# RFWBBoard.net
KiCad netlist of a schematic drawn in EAGLE
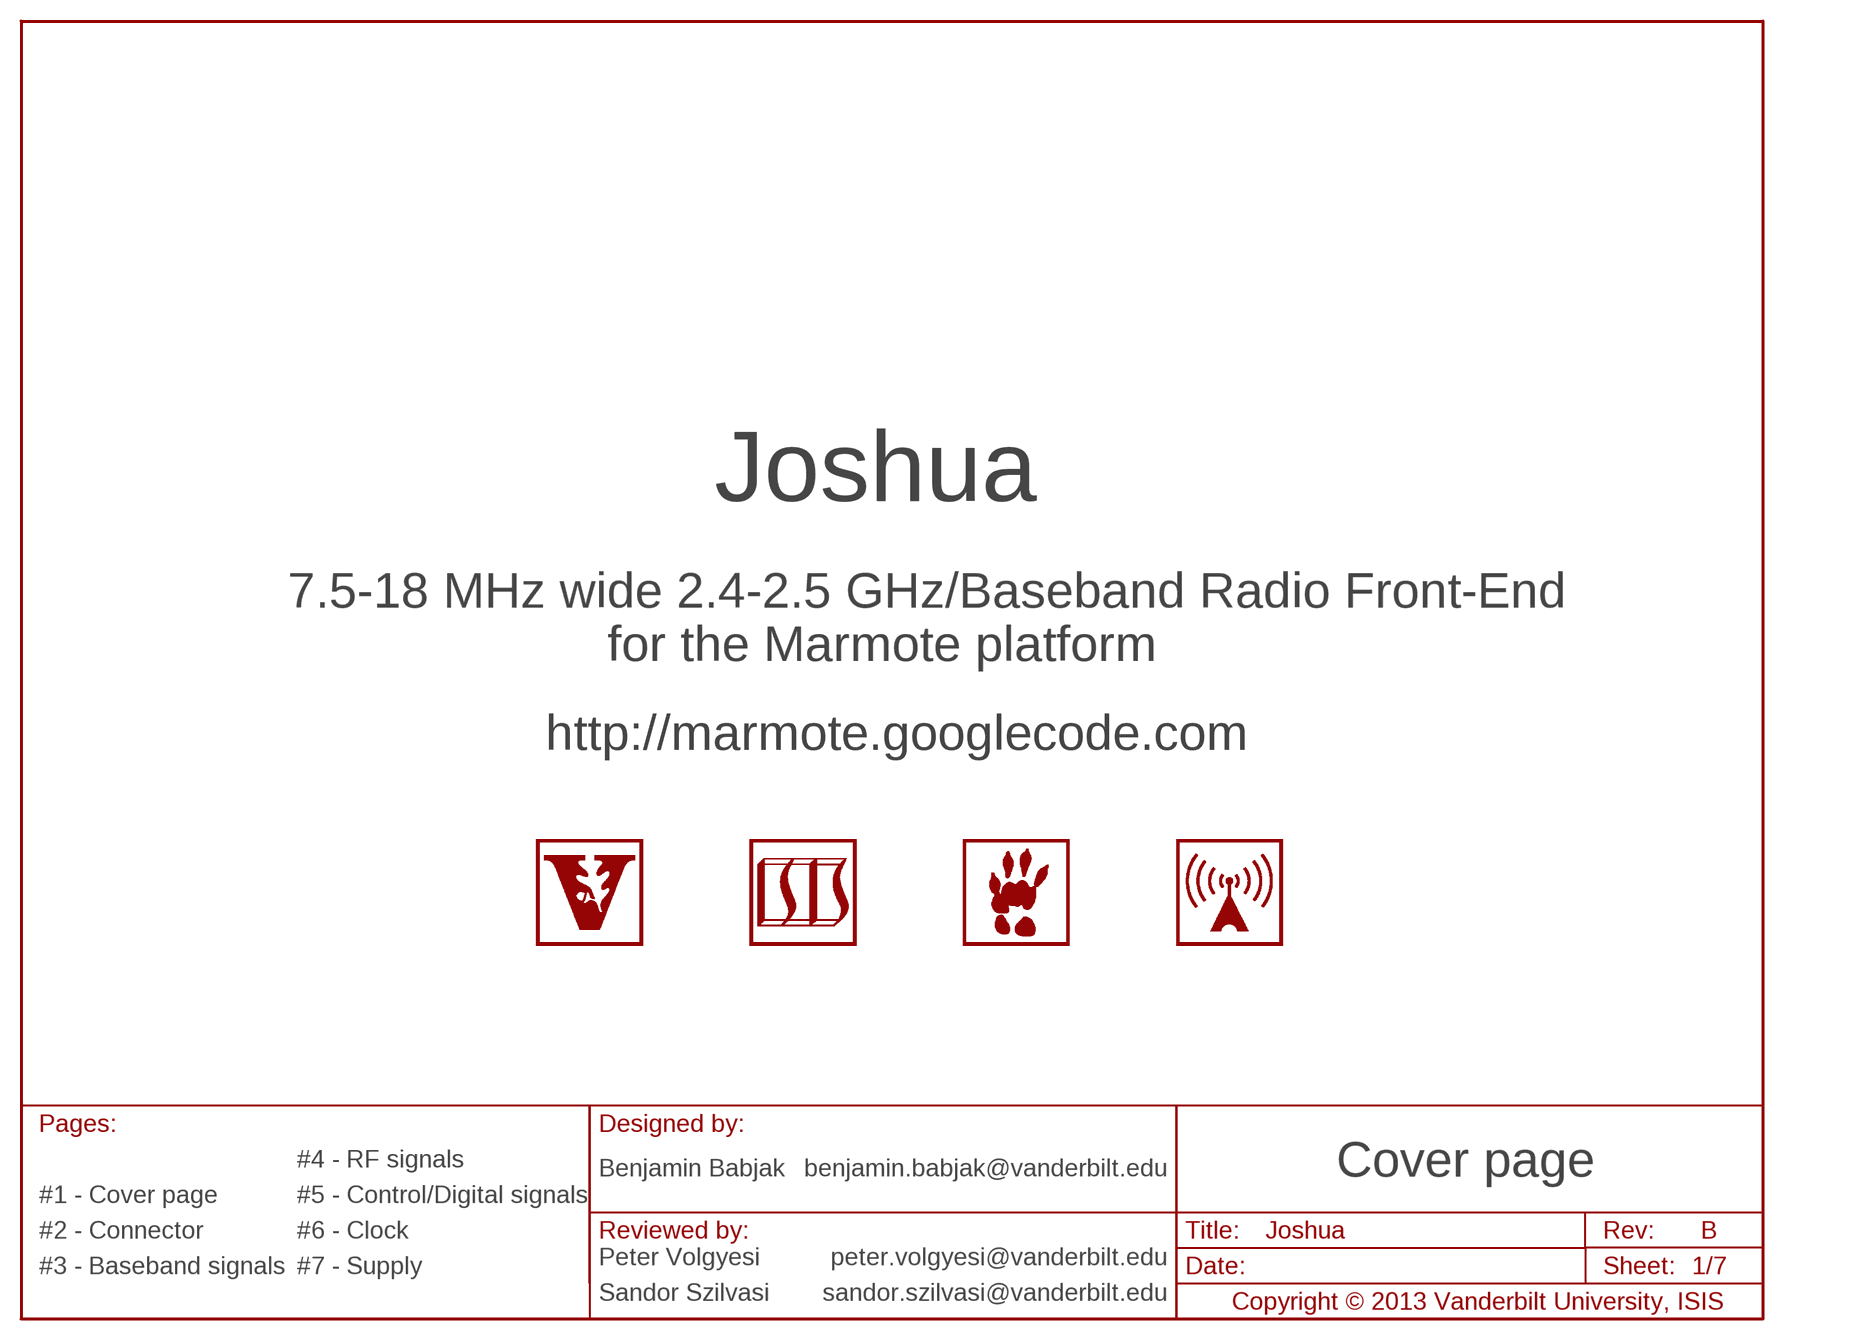
[diagram p0: schematic, sheet 1]
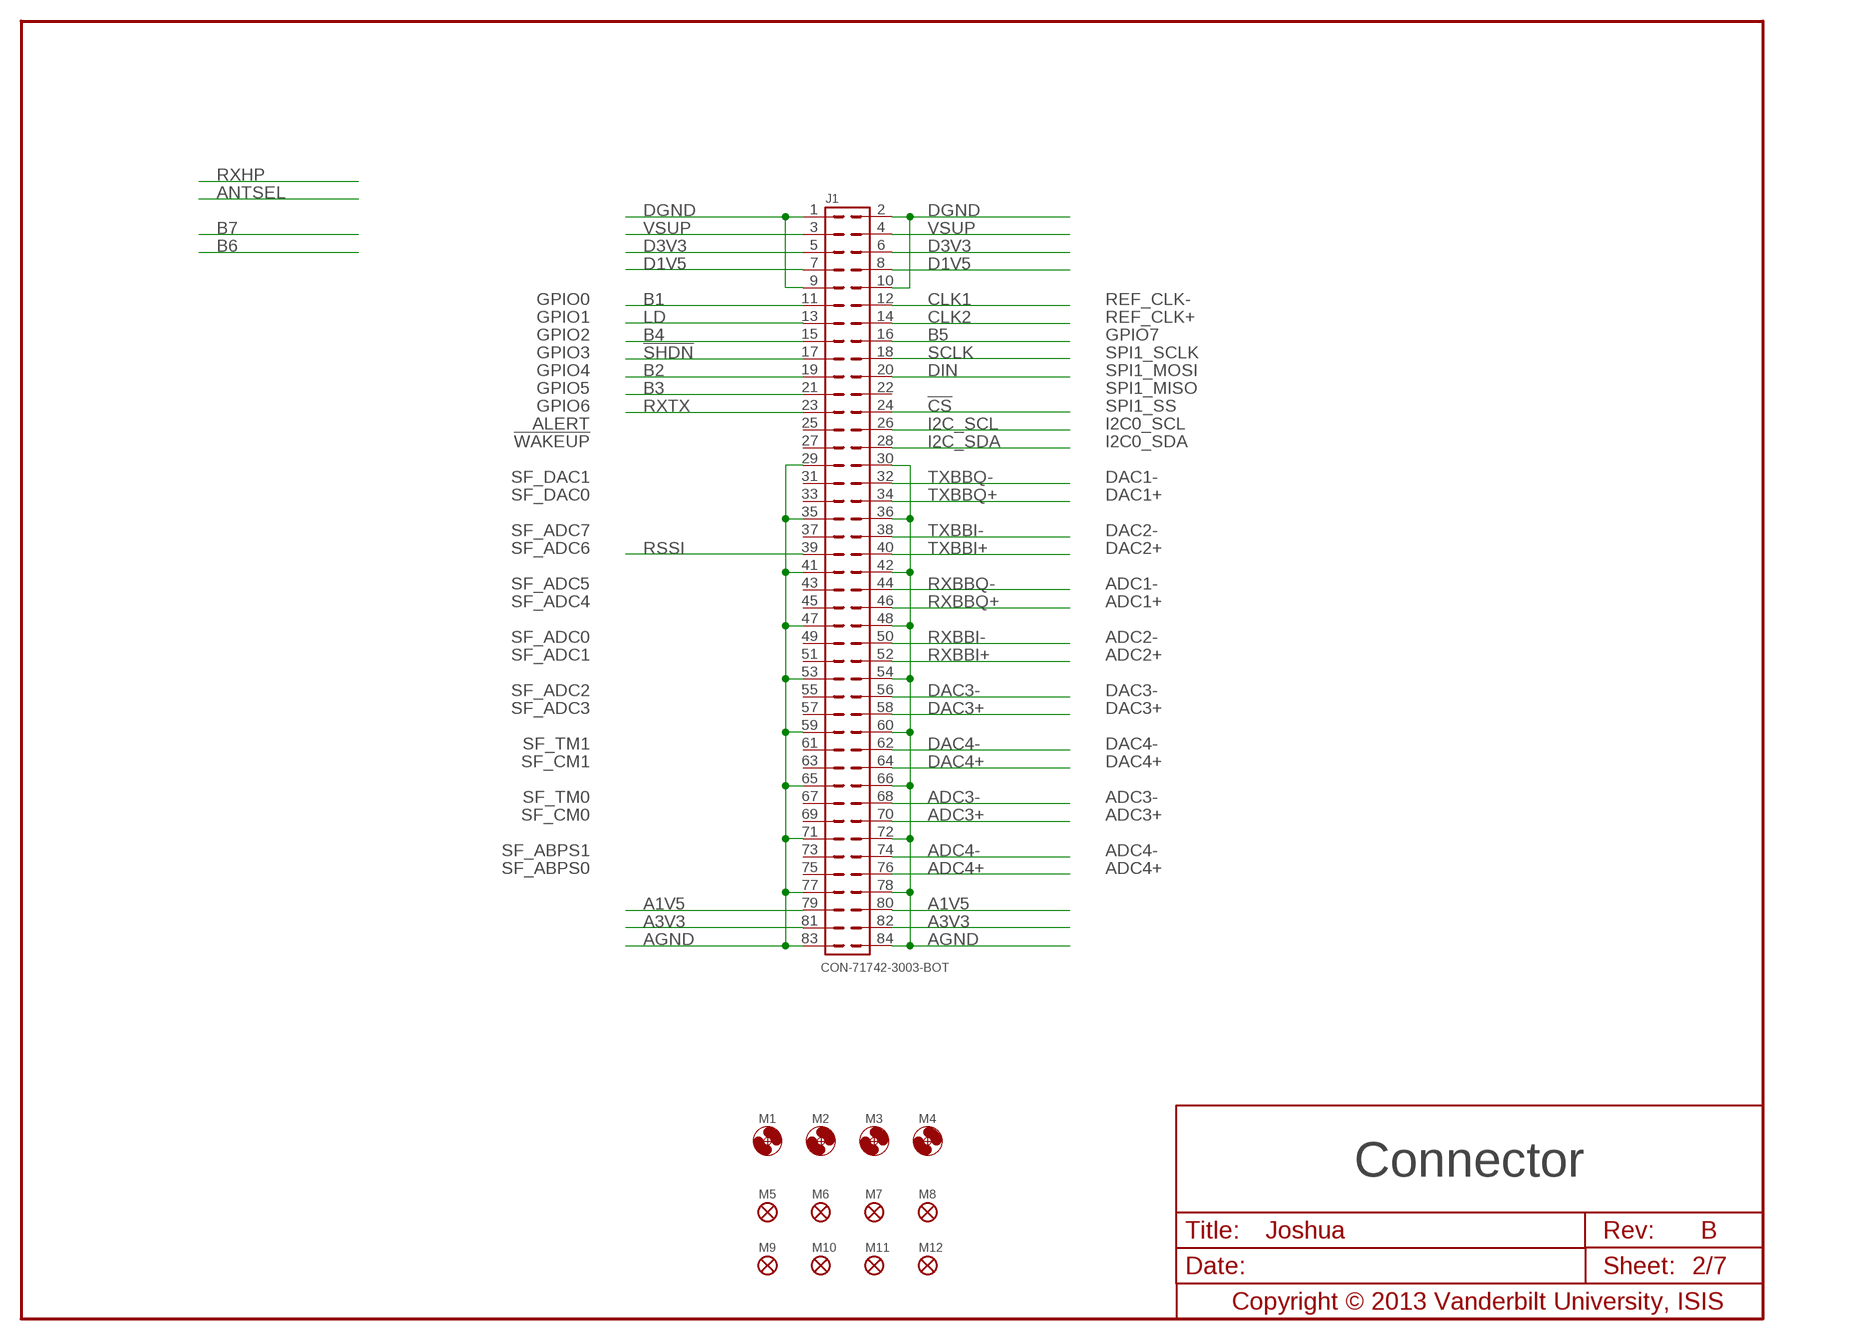
[diagram p1: schematic, sheet 2]
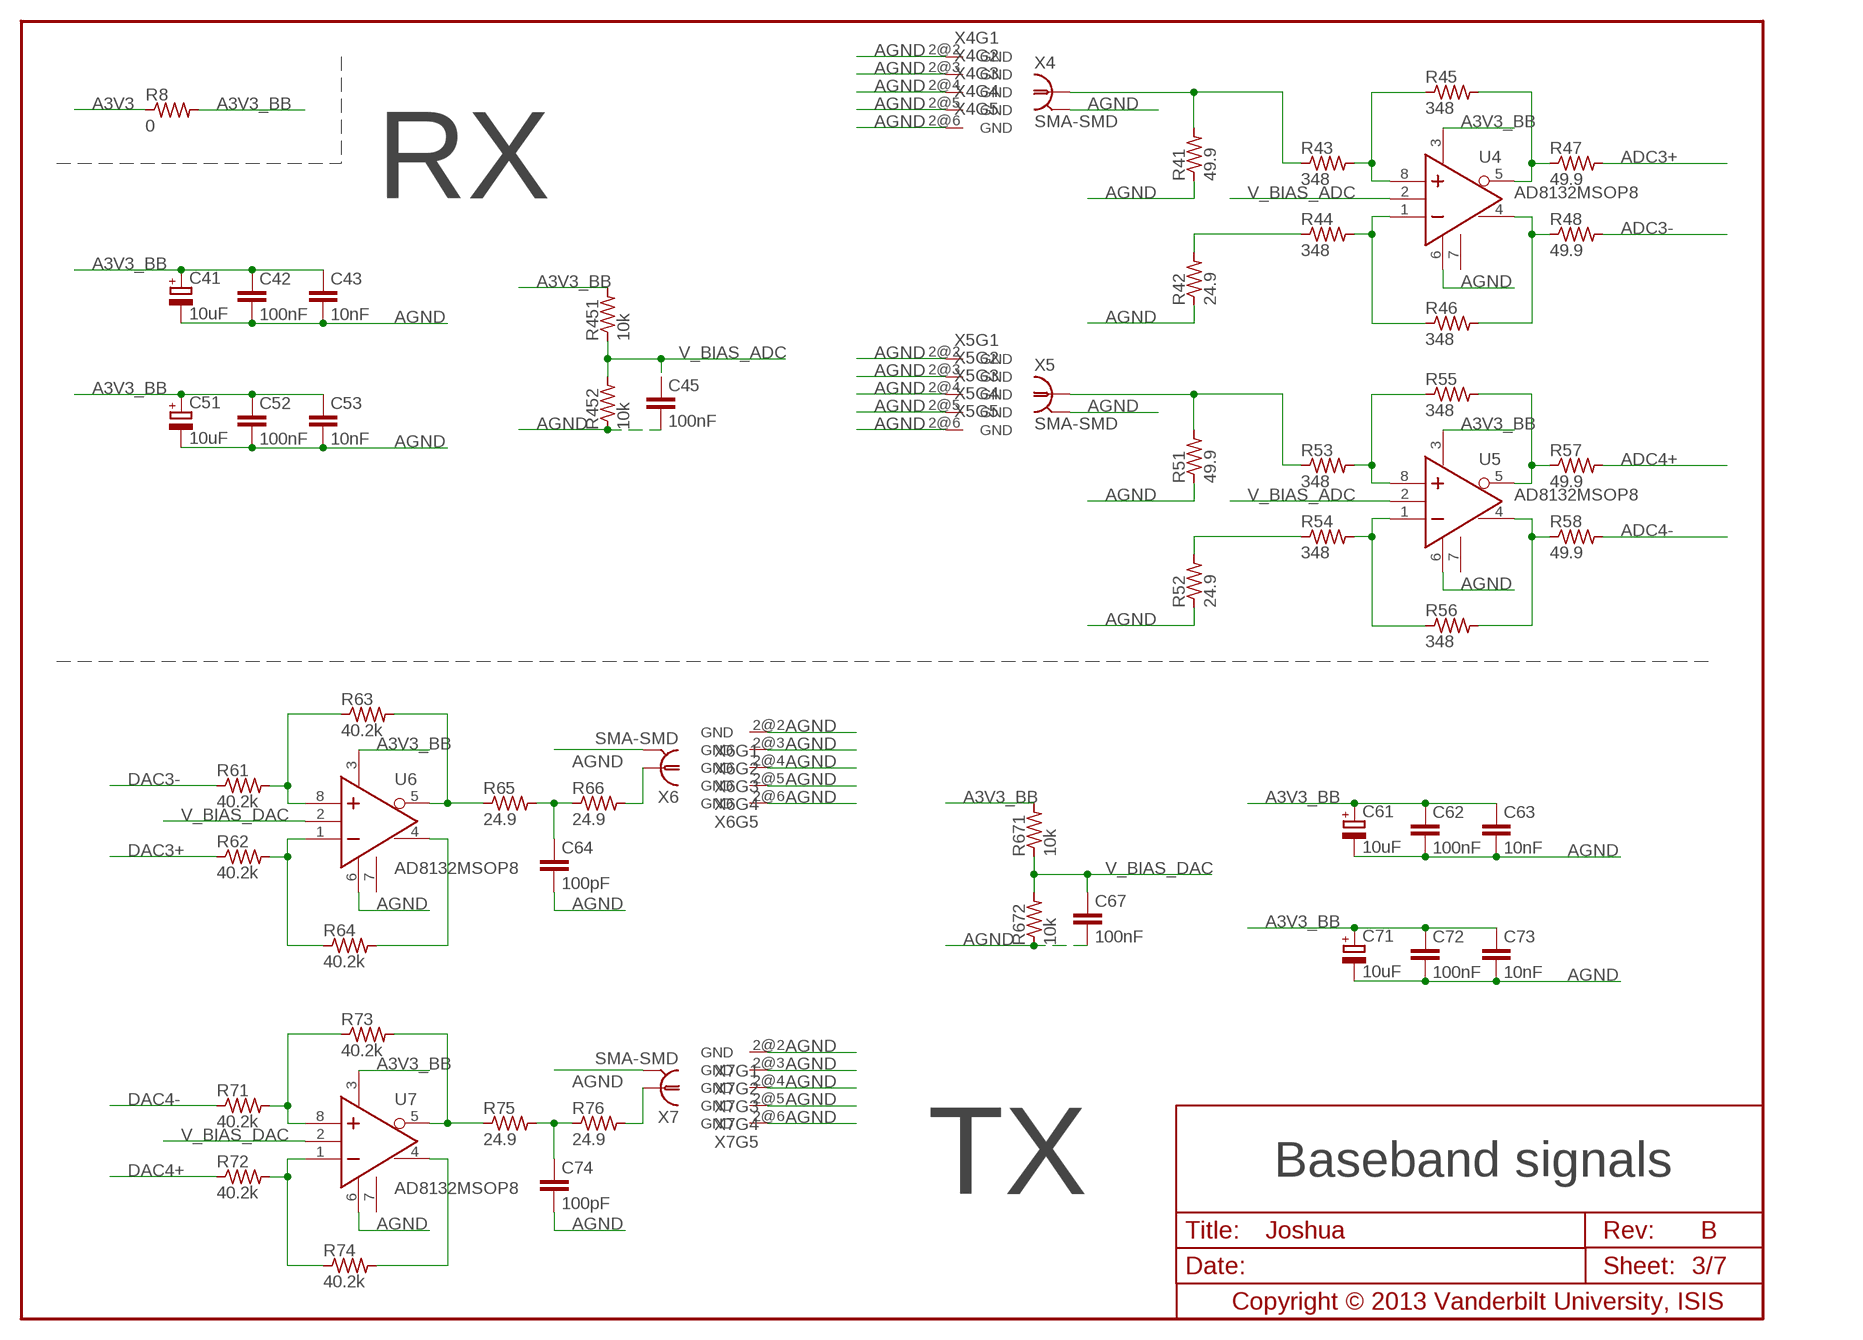
[diagram p2: schematic, sheet 3]
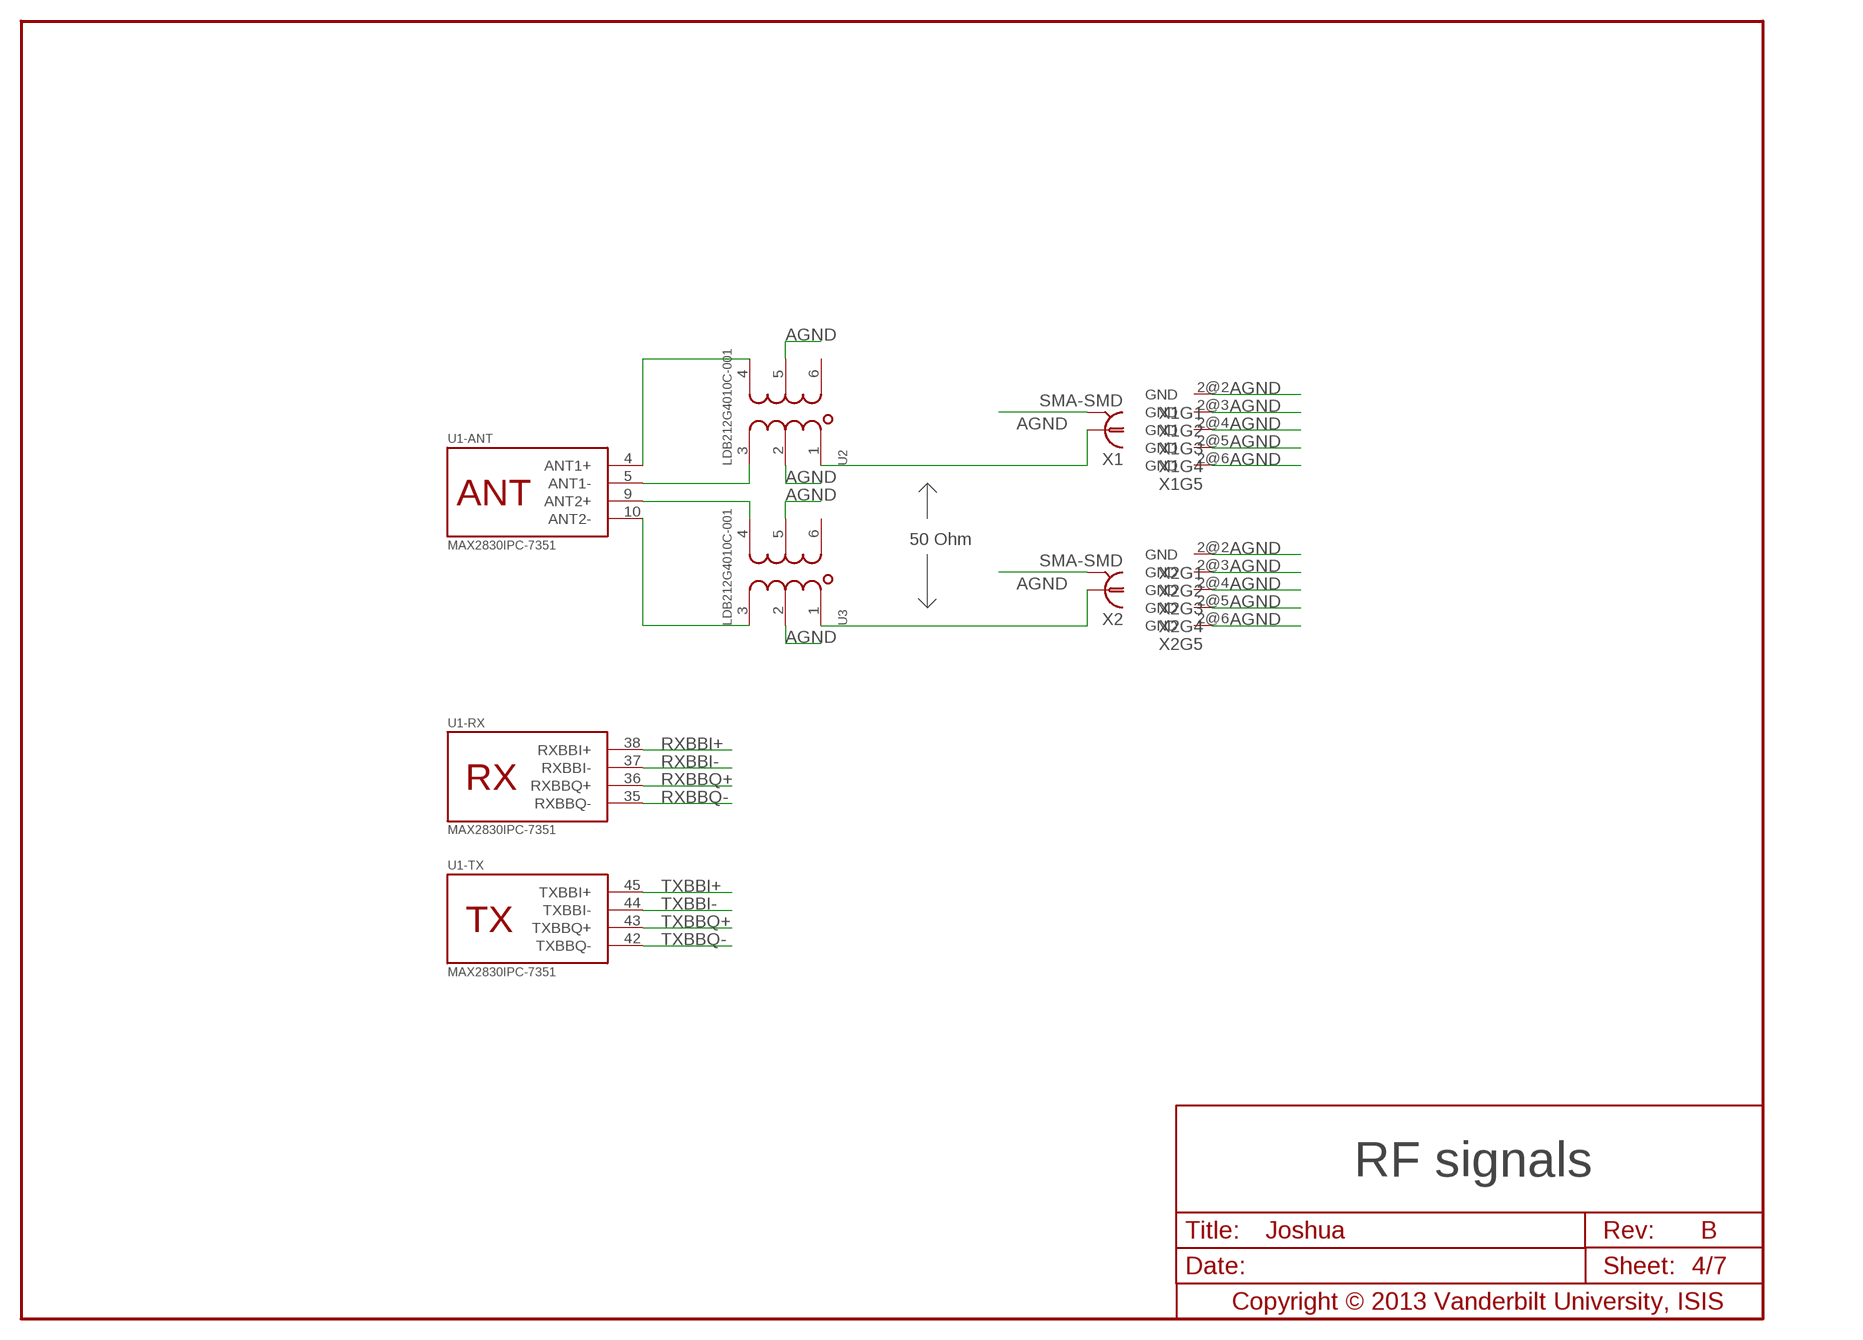
[diagram p3: schematic, sheet 4]
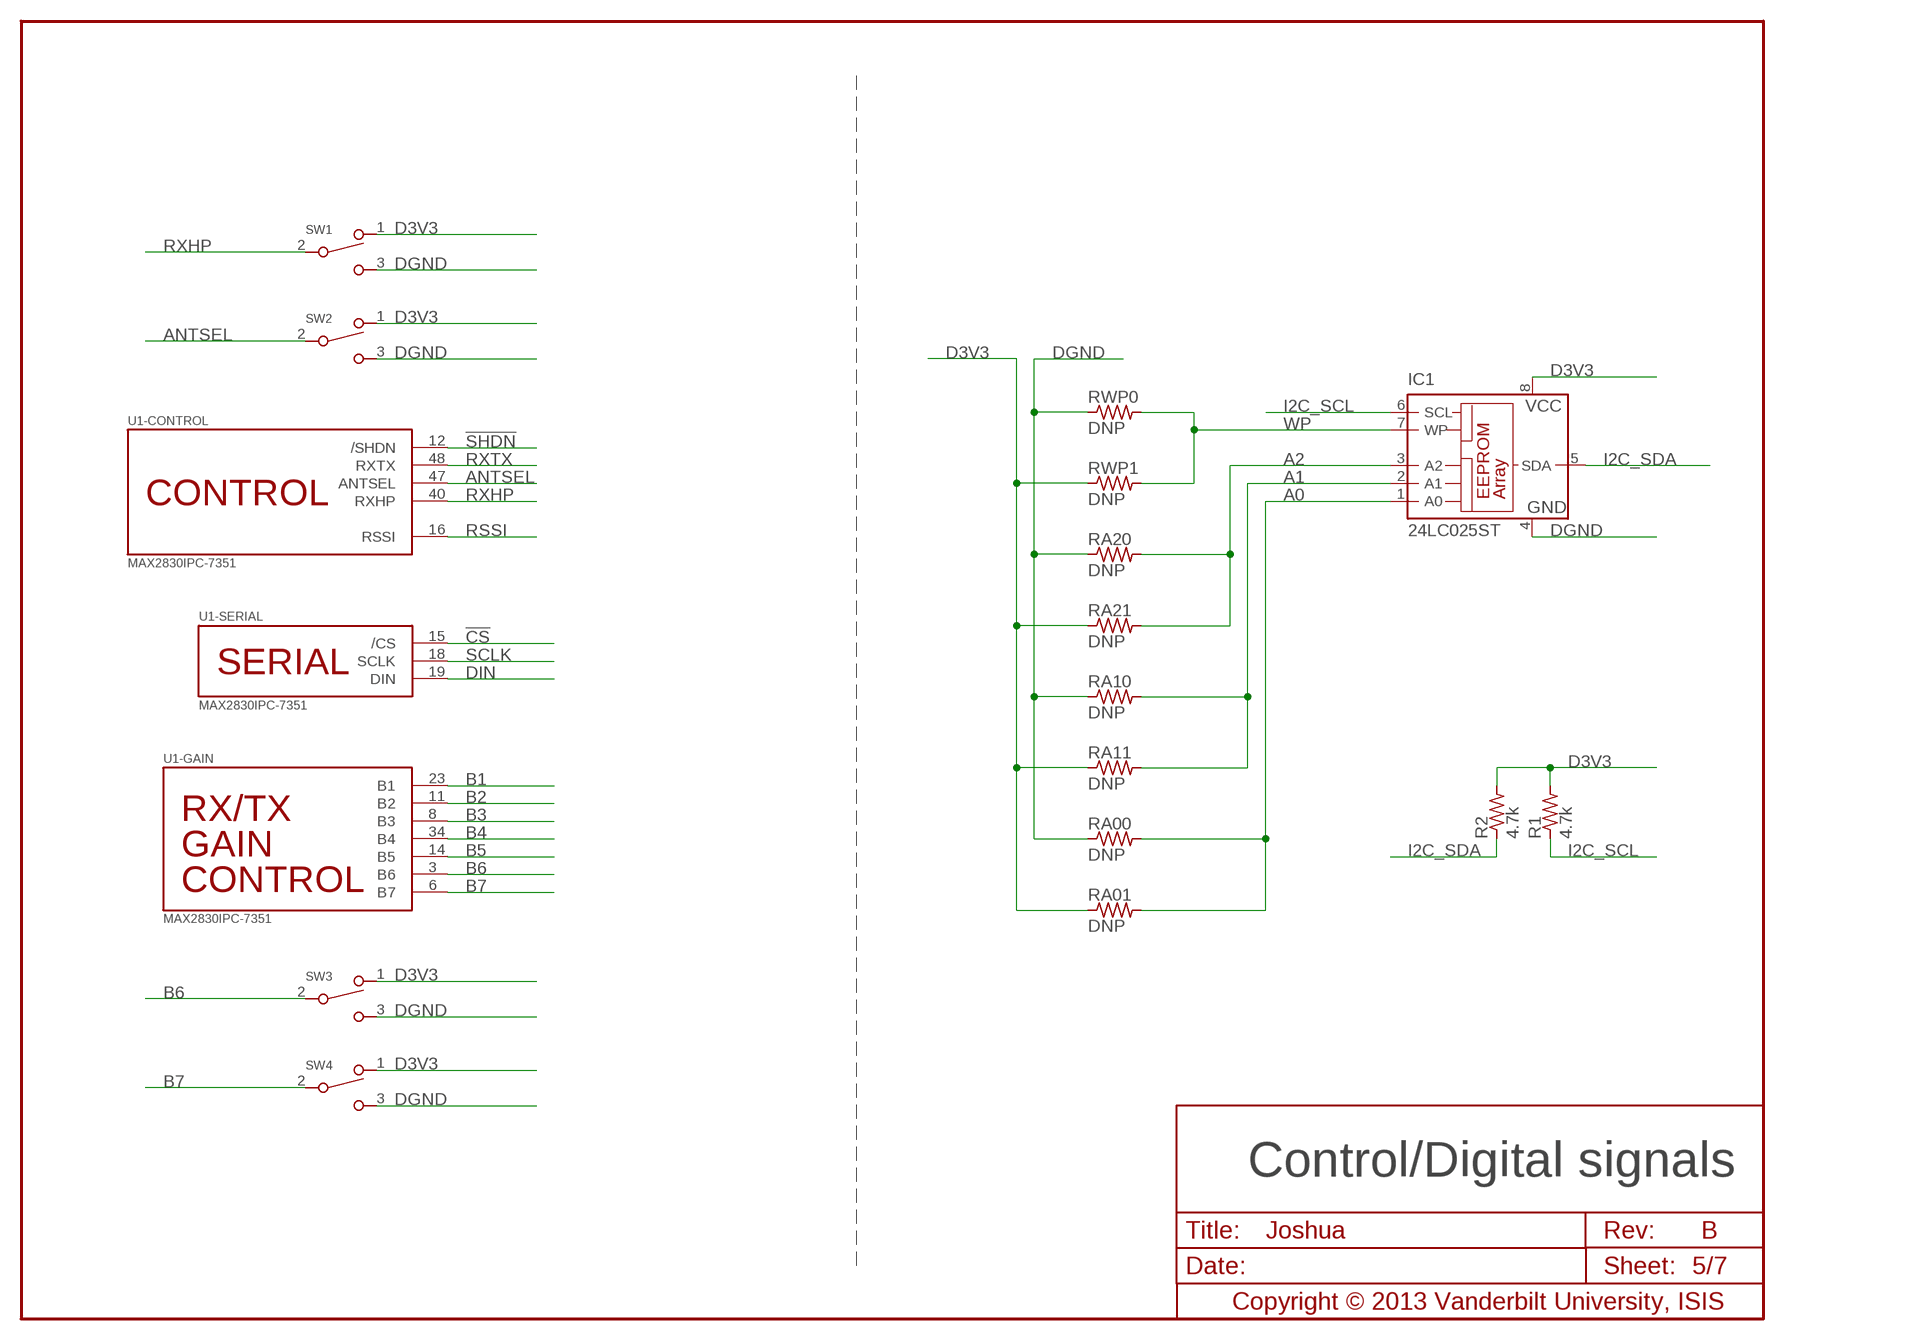
[diagram p4: schematic, sheet 5]
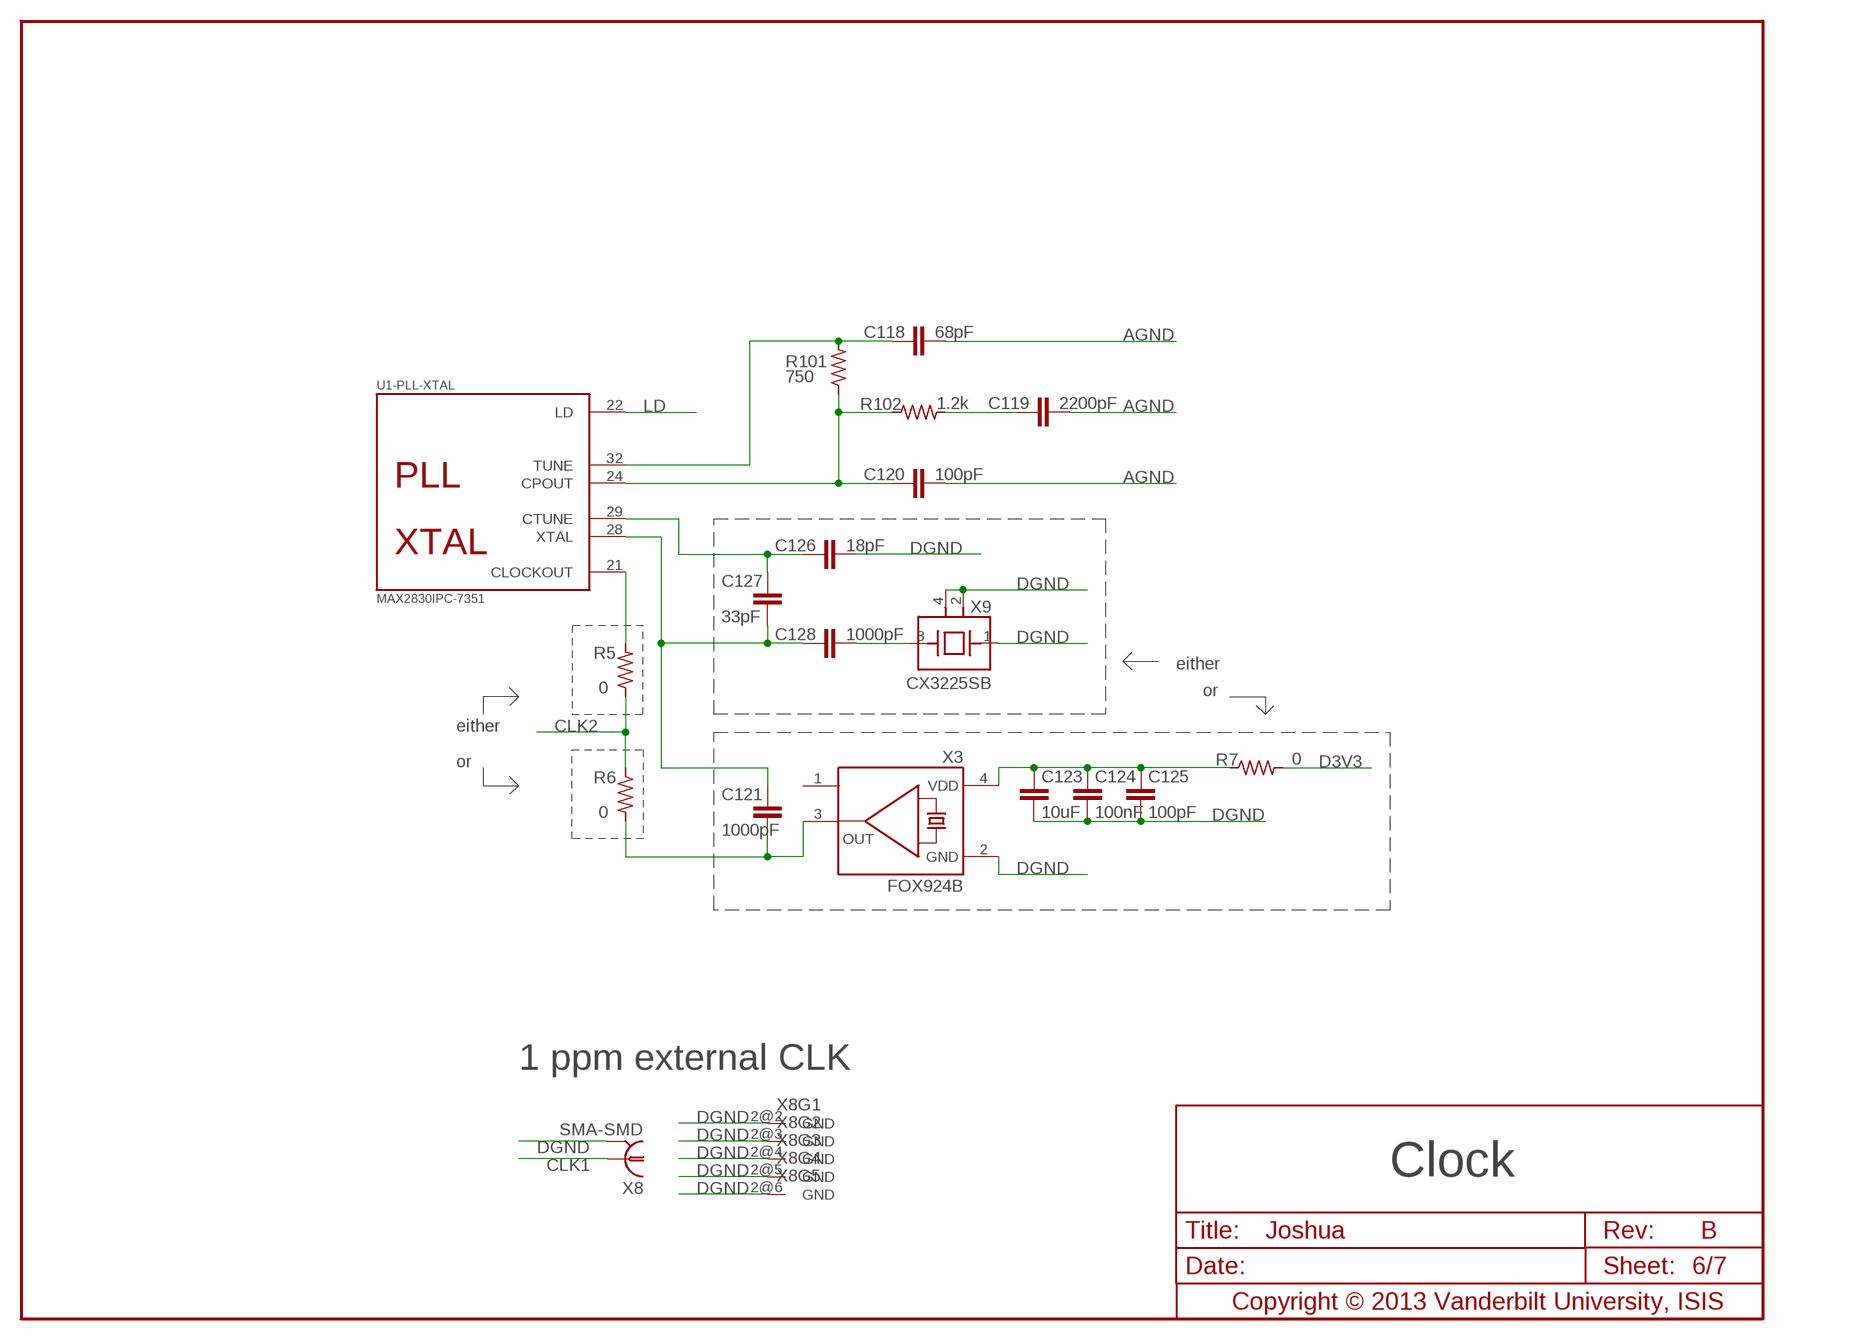
[diagram p5: schematic, sheet 6]
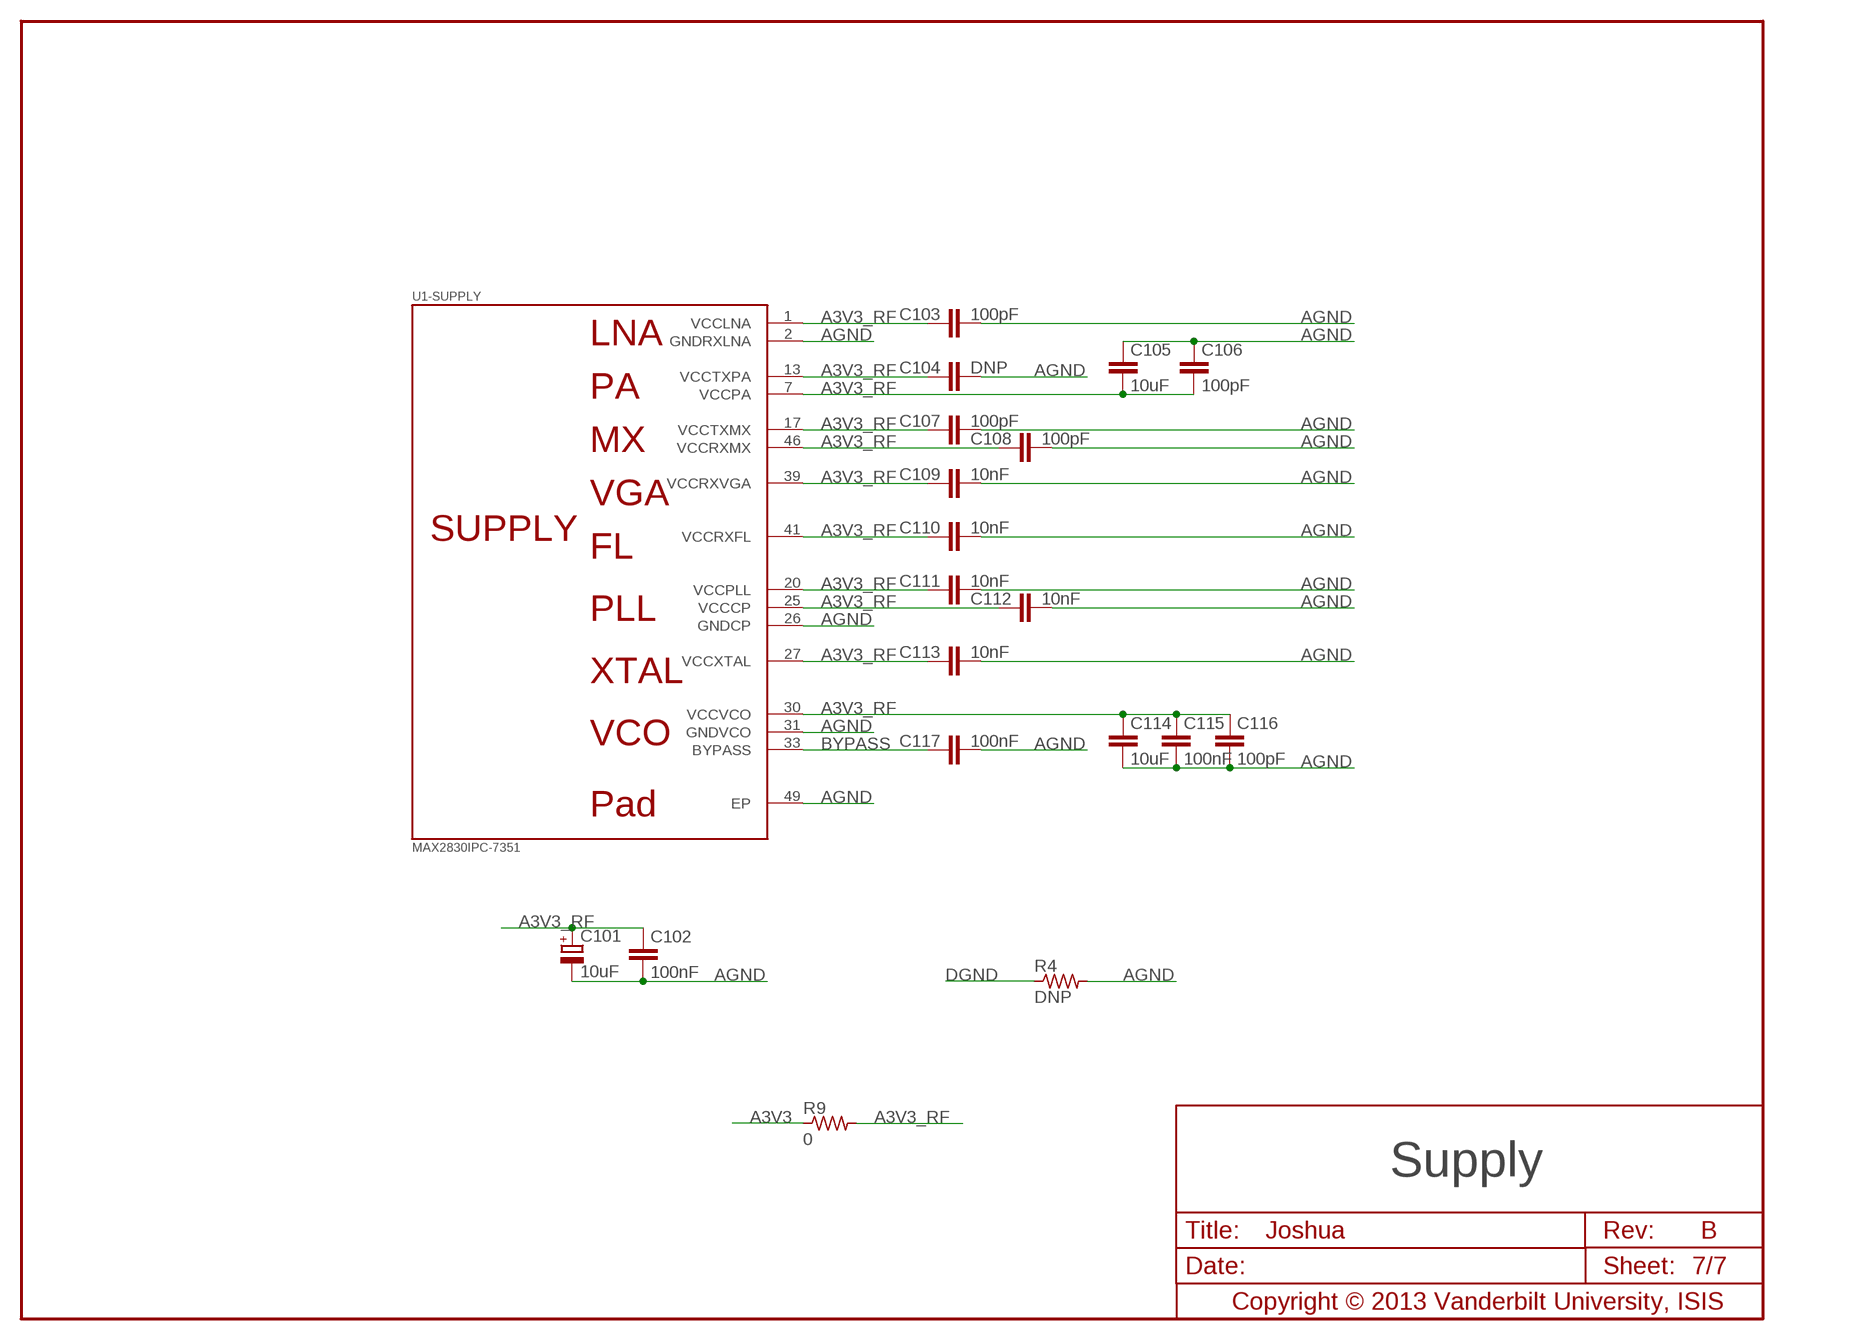
[diagram p6: schematic, sheet 7]

(export (version "E")
  (design (tool "Eeschema 10.0.6"))
  (components
    (comp (ref "LOGO4")
      (value "LOGO-ISIS-600MIL-10MM-SS")
      (footprint "eagle-import:LOGO-ISIS-10MM-SILKSCREEN")
      (libsource (lib "eagle-import") (part "LOGO-ISIS-600MIL-10MM-SS"))
    )
    (comp (ref "LOGO5")
      (value "LOGO-VANDERBILT-600MIL-10MM-SS")
      (footprint "eagle-import:LOGO-VANDERBILT-10MM-SILKSCREEN")
      (libsource (lib "eagle-import") (part "LOGO-VANDERBILT-600MIL-10MM-SS"))
    )
    (comp (ref "LOGO6")
      (value "LOGO-MARMOTE-600MIL-10MM-SS")
      (footprint "eagle-import:LOGO-MARMOTE-10MM-SILKSCREEN")
      (libsource (lib "eagle-import") (part "LOGO-MARMOTE-600MIL-10MM-SS"))
    )
    (comp (ref "LOGO7")
      (value "LOGO-RADIO-3-600MIL-10MM-SS")
      (footprint "eagle-import:LOGO-RADIO-FILLED-10MM-SILKSCREEN")
      (libsource (lib "eagle-import") (part "LOGO-RADIO-3-600MIL-10MM-SS"))
    )
    (comp (ref "U1")
      (value "MAX2830IPC-7351")
      (footprint "eagle-import:TQFN-48")
      (libsource (lib "eagle-import") (part "MAX2830IPC-7351"))
    )
    (comp (ref "U2")
      (value "LDB212G4010C-001")
      (footprint "eagle-import:LDB21-FOOTPRINT")
      (libsource (lib "eagle-import") (part "LDB212G4010C-001"))
    )
    (comp (ref "U3")
      (value "LDB212G4010C-001")
      (footprint "eagle-import:LDB21-FOOTPRINT")
      (libsource (lib "eagle-import") (part "LDB212G4010C-001"))
    )
    (comp (ref "X1")
      (value "SMA-SMD")
      (footprint "eagle-import:SMA-SMD")
      (libsource (lib "eagle-import") (part "SMA-SMD"))
    )
    (comp (ref "X2")
      (value "SMA-SMD")
      (footprint "eagle-import:SMA-SMD")
      (libsource (lib "eagle-import") (part "SMA-SMD"))
    )
    (comp (ref "J1")
      (value "CON-71742-3003-BOT")
      (footprint "eagle-import:71742-3003-BOT")
      (libsource (lib "eagle-import") (part "CON-71742-3003-BOT"))
    )
    (comp (ref "M1")
      (value "MOUNT-HOLE3.3")
      (footprint "eagle-import:3,3")
      (libsource (lib "eagle-import") (part "MOUNT-HOLE3.3"))
    )
    (comp (ref "M2")
      (value "MOUNT-HOLE3.3")
      (footprint "eagle-import:3,3")
      (libsource (lib "eagle-import") (part "MOUNT-HOLE3.3"))
    )
    (comp (ref "M3")
      (value "MOUNT-HOLE3.3")
      (footprint "eagle-import:3,3")
      (libsource (lib "eagle-import") (part "MOUNT-HOLE3.3"))
    )
    (comp (ref "M4")
      (value "MOUNT-HOLE3.3")
      (footprint "eagle-import:3,3")
      (libsource (lib "eagle-import") (part "MOUNT-HOLE3.3"))
    )
    (comp (ref "M5")
      (value "FIDUCIAL1X2")
      (footprint "eagle-import:FIDUCIAL-1X2")
      (libsource (lib "eagle-import") (part "FIDUCIAL1X2"))
    )
    (comp (ref "M6")
      (value "FIDUCIAL1X2")
      (footprint "eagle-import:FIDUCIAL-1X2")
      (libsource (lib "eagle-import") (part "FIDUCIAL1X2"))
    )
    (comp (ref "M7")
      (value "FIDUCIAL1X2")
      (footprint "eagle-import:FIDUCIAL-1X2")
      (libsource (lib "eagle-import") (part "FIDUCIAL1X2"))
    )
    (comp (ref "M8")
      (value "FIDUCIAL1X2")
      (footprint "eagle-import:FIDUCIAL-1X2")
      (libsource (lib "eagle-import") (part "FIDUCIAL1X2"))
    )
    (comp (ref "M9")
      (value "FIDUCIAL1X2")
      (footprint "eagle-import:FIDUCIAL-1X2")
      (libsource (lib "eagle-import") (part "FIDUCIAL1X2"))
    )
    (comp (ref "M10")
      (value "FIDUCIAL1X2")
      (footprint "eagle-import:FIDUCIAL-1X2")
      (libsource (lib "eagle-import") (part "FIDUCIAL1X2"))
    )
    (comp (ref "M11")
      (value "FIDUCIAL1X2")
      (footprint "eagle-import:FIDUCIAL-1X2")
      (libsource (lib "eagle-import") (part "FIDUCIAL1X2"))
    )
    (comp (ref "M12")
      (value "FIDUCIAL1X2")
      (footprint "eagle-import:FIDUCIAL-1X2")
      (libsource (lib "eagle-import") (part "FIDUCIAL1X2"))
    )
    (comp (ref "IC1")
      (value "24LC025ST")
      (footprint "eagle-import:TSSOP8")
      (fields (field (name "MF") "MICROCHIP") (field (name "MPN") "24LC025-I/ST"))
      (libsource (lib "eagle-import") (part "24STLC025"))
    )
    (comp (ref "R1")
      (value "4.7k")
      (footprint "eagle-import:R0402")
      (libsource (lib "eagle-import") (part "R0402"))
    )
    (comp (ref "R2")
      (value "4.7k")
      (footprint "eagle-import:R0402")
      (libsource (lib "eagle-import") (part "R0402"))
    )
    (comp (ref "RA00")
      (value "DNP")
      (footprint "eagle-import:R0402")
      (libsource (lib "eagle-import") (part "R0402"))
    )
    (comp (ref "RA01")
      (value "DNP")
      (footprint "eagle-import:R0402")
      (libsource (lib "eagle-import") (part "R0402"))
    )
    (comp (ref "RA10")
      (value "DNP")
      (footprint "eagle-import:R0402")
      (libsource (lib "eagle-import") (part "R0402"))
    )
    (comp (ref "RA11")
      (value "DNP")
      (footprint "eagle-import:R0402")
      (libsource (lib "eagle-import") (part "R0402"))
    )
    (comp (ref "RA20")
      (value "DNP")
      (footprint "eagle-import:R0402")
      (libsource (lib "eagle-import") (part "R0402"))
    )
    (comp (ref "RA21")
      (value "DNP")
      (footprint "eagle-import:R0402")
      (libsource (lib "eagle-import") (part "R0402"))
    )
    (comp (ref "RWP0")
      (value "DNP")
      (footprint "eagle-import:R0402")
      (libsource (lib "eagle-import") (part "R0402"))
    )
    (comp (ref "RWP1")
      (value "DNP")
      (footprint "eagle-import:R0402")
      (libsource (lib "eagle-import") (part "R0402"))
    )
    (comp (ref "SW1")
      (value "SWITCH-CJS-1200TA")
      (footprint "eagle-import:SWITCH-DIP-CJS")
      (fields (field (name "MF") "CJS") (field (name "MPN") "CJS-1200TA"))
      (libsource (lib "eagle-import") (part "SWITCH-CJS-1200TA"))
    )
    (comp (ref "SW2")
      (value "SWITCH-CJS-1200TA")
      (footprint "eagle-import:SWITCH-DIP-CJS")
      (fields (field (name "MF") "CJS") (field (name "MPN") "CJS-1200TA"))
      (libsource (lib "eagle-import") (part "SWITCH-CJS-1200TA"))
    )
    (comp (ref "SW3")
      (value "SWITCH-CJS-1200TA")
      (footprint "eagle-import:SWITCH-DIP-CJS")
      (fields (field (name "MF") "CJS") (field (name "MPN") "CJS-1200TA"))
      (libsource (lib "eagle-import") (part "SWITCH-CJS-1200TA"))
    )
    (comp (ref "SW4")
      (value "SWITCH-CJS-1200TA")
      (footprint "eagle-import:SWITCH-DIP-CJS")
      (fields (field (name "MF") "CJS") (field (name "MPN") "CJS-1200TA"))
      (libsource (lib "eagle-import") (part "SWITCH-CJS-1200TA"))
    )
    (comp (ref "C101")
      (value "10uF")
      (footprint "eagle-import:CPOL2012")
      (libsource (lib "eagle-import") (part "CPOL2012"))
    )
    (comp (ref "C102")
      (value "100nF")
      (footprint "eagle-import:C0402")
      (libsource (lib "eagle-import") (part "C0402"))
    )
    (comp (ref "C103")
      (value "100pF")
      (footprint "eagle-import:C0402")
      (libsource (lib "eagle-import") (part "C0402"))
    )
    (comp (ref "C104")
      (value "DNP")
      (footprint "eagle-import:C0402")
      (libsource (lib "eagle-import") (part "C0402"))
    )
    (comp (ref "C105")
      (value "10uF")
      (footprint "eagle-import:C1206")
      (libsource (lib "eagle-import") (part "C1206"))
    )
    (comp (ref "C106")
      (value "100pF")
      (footprint "eagle-import:C0402")
      (libsource (lib "eagle-import") (part "C0402"))
    )
    (comp (ref "C107")
      (value "100pF")
      (footprint "eagle-import:C0402")
      (libsource (lib "eagle-import") (part "C0402"))
    )
    (comp (ref "C108")
      (value "100pF")
      (footprint "eagle-import:C0402")
      (libsource (lib "eagle-import") (part "C0402"))
    )
    (comp (ref "C109")
      (value "10nF")
      (footprint "eagle-import:C0402")
      (libsource (lib "eagle-import") (part "C0402"))
    )
    (comp (ref "C110")
      (value "10nF")
      (footprint "eagle-import:C0402")
      (libsource (lib "eagle-import") (part "C0402"))
    )
    (comp (ref "C111")
      (value "10nF")
      (footprint "eagle-import:C0402")
      (libsource (lib "eagle-import") (part "C0402"))
    )
    (comp (ref "C112")
      (value "10nF")
      (footprint "eagle-import:C0402")
      (libsource (lib "eagle-import") (part "C0402"))
    )
    (comp (ref "C113")
      (value "10nF")
      (footprint "eagle-import:C0402")
      (libsource (lib "eagle-import") (part "C0402"))
    )
    (comp (ref "C114")
      (value "10uF")
      (footprint "eagle-import:C0805")
      (libsource (lib "eagle-import") (part "C0805"))
    )
    (comp (ref "C115")
      (value "100nF")
      (footprint "eagle-import:C0402")
      (libsource (lib "eagle-import") (part "C0402"))
    )
    (comp (ref "C116")
      (value "100pF")
      (footprint "eagle-import:C0402")
      (libsource (lib "eagle-import") (part "C0402"))
    )
    (comp (ref "C117")
      (value "100nF")
      (footprint "eagle-import:C0402")
      (libsource (lib "eagle-import") (part "C0402"))
    )
    (comp (ref "R4")
      (value "DNP")
      (footprint "eagle-import:R1206")
      (libsource (lib "eagle-import") (part "R1206"))
    )
    (comp (ref "R9")
      (value "0")
      (footprint "eagle-import:R1206")
      (libsource (lib "eagle-import") (part "R1206"))
    )
    (comp (ref "C118")
      (value "68pF")
      (footprint "eagle-import:C0402")
      (libsource (lib "eagle-import") (part "C0402"))
    )
    (comp (ref "C119")
      (value "2200pF")
      (footprint "eagle-import:C0402")
      (libsource (lib "eagle-import") (part "C0402"))
    )
    (comp (ref "C120")
      (value "100pF")
      (footprint "eagle-import:C0402")
      (libsource (lib "eagle-import") (part "C0402"))
    )
    (comp (ref "C121")
      (value "1000pF")
      (footprint "eagle-import:C0402")
      (libsource (lib "eagle-import") (part "C0402"))
    )
    (comp (ref "C123")
      (value "10uF")
      (footprint "eagle-import:C0805")
      (libsource (lib "eagle-import") (part "C0805"))
    )
    (comp (ref "C124")
      (value "100nF")
      (footprint "eagle-import:C0402")
      (libsource (lib "eagle-import") (part "C0402"))
    )
    (comp (ref "C125")
      (value "100pF")
      (footprint "eagle-import:C0402")
      (libsource (lib "eagle-import") (part "C0402"))
    )
    (comp (ref "C126")
      (value "18pF")
      (footprint "eagle-import:C0402")
      (libsource (lib "eagle-import") (part "C0402"))
    )
    (comp (ref "C127")
      (value "33pF")
      (footprint "eagle-import:C0402")
      (libsource (lib "eagle-import") (part "C0402"))
    )
    (comp (ref "C128")
      (value "1000pF")
      (footprint "eagle-import:C0402")
      (libsource (lib "eagle-import") (part "C0402"))
    )
    (comp (ref "R5")
      (value "0")
      (footprint "eagle-import:R0402")
      (libsource (lib "eagle-import") (part "R0402"))
    )
    (comp (ref "R6")
      (value "0")
      (footprint "eagle-import:R0402")
      (libsource (lib "eagle-import") (part "R0402"))
    )
    (comp (ref "R7")
      (value "0")
      (footprint "eagle-import:R1206")
      (libsource (lib "eagle-import") (part "R1206"))
    )
    (comp (ref "R101")
      (value "750")
      (footprint "eagle-import:R0402")
      (libsource (lib "eagle-import") (part "R0402"))
    )
    (comp (ref "R102")
      (value "1.2k")
      (footprint "eagle-import:R0402")
      (libsource (lib "eagle-import") (part "R0402"))
    )
    (comp (ref "X3")
      (value "FOX924B")
      (footprint "eagle-import:FOX924")
      (fields (field (name "MF") "Fox Electronics") (field (name "MPN") "FOX924B-20.000"))
      (libsource (lib "eagle-import") (part "FOX924B"))
    )
    (comp (ref "X8")
      (value "SMA-SMD")
      (footprint "eagle-import:SMA-SMD")
      (libsource (lib "eagle-import") (part "SMA-SMD"))
    )
    (comp (ref "X9")
      (value "CX3225SB")
      (footprint "eagle-import:CX3225SB")
      (libsource (lib "eagle-import") (part "CX3225SB"))
    )
    (comp (ref "C41")
      (value "10uF")
      (footprint "eagle-import:CPOL2012")
      (libsource (lib "eagle-import") (part "CPOL2012"))
    )
    (comp (ref "C42")
      (value "100nF")
      (footprint "eagle-import:C0402")
      (libsource (lib "eagle-import") (part "C0402"))
    )
    (comp (ref "C43")
      (value "10nF")
      (footprint "eagle-import:C0402")
      (libsource (lib "eagle-import") (part "C0402"))
    )
    (comp (ref "C45")
      (value "100nF")
      (footprint "eagle-import:C0402")
      (libsource (lib "eagle-import") (part "C0402"))
    )
    (comp (ref "C51")
      (value "10uF")
      (footprint "eagle-import:CPOL2012")
      (libsource (lib "eagle-import") (part "CPOL2012"))
    )
    (comp (ref "C52")
      (value "100nF")
      (footprint "eagle-import:C0402")
      (libsource (lib "eagle-import") (part "C0402"))
    )
    (comp (ref "C53")
      (value "10nF")
      (footprint "eagle-import:C0402")
      (libsource (lib "eagle-import") (part "C0402"))
    )
    (comp (ref "C61")
      (value "10uF")
      (footprint "eagle-import:CPOL2012")
      (libsource (lib "eagle-import") (part "CPOL2012"))
    )
    (comp (ref "C62")
      (value "100nF")
      (footprint "eagle-import:C0402")
      (libsource (lib "eagle-import") (part "C0402"))
    )
    (comp (ref "C63")
      (value "10nF")
      (footprint "eagle-import:C0402")
      (libsource (lib "eagle-import") (part "C0402"))
    )
    (comp (ref "C64")
      (value "100pF")
      (footprint "eagle-import:C0402")
      (libsource (lib "eagle-import") (part "C0402"))
    )
    (comp (ref "C67")
      (value "100nF")
      (footprint "eagle-import:C0402")
      (libsource (lib "eagle-import") (part "C0402"))
    )
    (comp (ref "C71")
      (value "10uF")
      (footprint "eagle-import:CPOL2012")
      (libsource (lib "eagle-import") (part "CPOL2012"))
    )
    (comp (ref "C72")
      (value "100nF")
      (footprint "eagle-import:C0402")
      (libsource (lib "eagle-import") (part "C0402"))
    )
    (comp (ref "C73")
      (value "10nF")
      (footprint "eagle-import:C0402")
      (libsource (lib "eagle-import") (part "C0402"))
    )
    (comp (ref "C74")
      (value "100pF")
      (footprint "eagle-import:C0402")
      (libsource (lib "eagle-import") (part "C0402"))
    )
    (comp (ref "R8")
      (value "0")
      (footprint "eagle-import:R1206")
      (libsource (lib "eagle-import") (part "R1206"))
    )
    (comp (ref "R41")
      (value "49.9")
      (footprint "eagle-import:R0402")
      (libsource (lib "eagle-import") (part "R0402"))
    )
    (comp (ref "R42")
      (value "24.9")
      (footprint "eagle-import:R0402")
      (libsource (lib "eagle-import") (part "R0402"))
    )
    (comp (ref "R43")
      (value "348")
      (footprint "eagle-import:R0402")
      (libsource (lib "eagle-import") (part "R0402"))
    )
    (comp (ref "R44")
      (value "348")
      (footprint "eagle-import:R0402")
      (libsource (lib "eagle-import") (part "R0402"))
    )
    (comp (ref "R45")
      (value "348")
      (footprint "eagle-import:R0402")
      (libsource (lib "eagle-import") (part "R0402"))
    )
    (comp (ref "R46")
      (value "348")
      (footprint "eagle-import:R0402")
      (libsource (lib "eagle-import") (part "R0402"))
    )
    (comp (ref "R47")
      (value "49.9")
      (footprint "eagle-import:R0402")
      (libsource (lib "eagle-import") (part "R0402"))
    )
    (comp (ref "R48")
      (value "49.9")
      (footprint "eagle-import:R0402")
      (libsource (lib "eagle-import") (part "R0402"))
    )
    (comp (ref "R51")
      (value "49.9")
      (footprint "eagle-import:R0402")
      (libsource (lib "eagle-import") (part "R0402"))
    )
    (comp (ref "R52")
      (value "24.9")
      (footprint "eagle-import:R0402")
      (libsource (lib "eagle-import") (part "R0402"))
    )
    (comp (ref "R53")
      (value "348")
      (footprint "eagle-import:R0402")
      (libsource (lib "eagle-import") (part "R0402"))
    )
    (comp (ref "R54")
      (value "348")
      (footprint "eagle-import:R0402")
      (libsource (lib "eagle-import") (part "R0402"))
    )
    (comp (ref "R55")
      (value "348")
      (footprint "eagle-import:R0402")
      (libsource (lib "eagle-import") (part "R0402"))
    )
    (comp (ref "R56")
      (value "348")
      (footprint "eagle-import:R0402")
      (libsource (lib "eagle-import") (part "R0402"))
    )
    (comp (ref "R57")
      (value "49.9")
      (footprint "eagle-import:R0402")
      (libsource (lib "eagle-import") (part "R0402"))
    )
    (comp (ref "R58")
      (value "49.9")
      (footprint "eagle-import:R0402")
      (libsource (lib "eagle-import") (part "R0402"))
    )
    (comp (ref "R61")
      (value "40.2k")
      (footprint "eagle-import:R0402")
      (libsource (lib "eagle-import") (part "R0402"))
    )
    (comp (ref "R62")
      (value "40.2k")
      (footprint "eagle-import:R0402")
      (libsource (lib "eagle-import") (part "R0402"))
    )
    (comp (ref "R63")
      (value "40.2k")
      (footprint "eagle-import:R0402")
      (libsource (lib "eagle-import") (part "R0402"))
    )
    (comp (ref "R64")
      (value "40.2k")
      (footprint "eagle-import:R0402")
      (libsource (lib "eagle-import") (part "R0402"))
    )
    (comp (ref "R65")
      (value "24.9")
      (footprint "eagle-import:R0402")
      (libsource (lib "eagle-import") (part "R0402"))
    )
    (comp (ref "R66")
      (value "24.9")
      (footprint "eagle-import:R0402")
      (libsource (lib "eagle-import") (part "R0402"))
    )
    (comp (ref "R71")
      (value "40.2k")
      (footprint "eagle-import:R0402")
      (libsource (lib "eagle-import") (part "R0402"))
    )
    (comp (ref "R72")
      (value "40.2k")
      (footprint "eagle-import:R0402")
      (libsource (lib "eagle-import") (part "R0402"))
    )
    (comp (ref "R73")
      (value "40.2k")
      (footprint "eagle-import:R0402")
      (libsource (lib "eagle-import") (part "R0402"))
    )
    (comp (ref "R74")
      (value "40.2k")
      (footprint "eagle-import:R0402")
      (libsource (lib "eagle-import") (part "R0402"))
    )
    (comp (ref "R75")
      (value "24.9")
      (footprint "eagle-import:R0402")
      (libsource (lib "eagle-import") (part "R0402"))
    )
    (comp (ref "R76")
      (value "24.9")
      (footprint "eagle-import:R0402")
      (libsource (lib "eagle-import") (part "R0402"))
    )
    (comp (ref "R451")
      (value "10k")
      (footprint "eagle-import:R0402")
      (libsource (lib "eagle-import") (part "R0402"))
    )
    (comp (ref "R452")
      (value "10k")
      (footprint "eagle-import:R0402")
      (libsource (lib "eagle-import") (part "R0402"))
    )
    (comp (ref "R671")
      (value "10k")
      (footprint "eagle-import:R0402")
      (libsource (lib "eagle-import") (part "R0402"))
    )
    (comp (ref "R672")
      (value "10k")
      (footprint "eagle-import:R0402")
      (libsource (lib "eagle-import") (part "R0402"))
    )
    (comp (ref "U4")
      (value "AD8132MSOP8")
      (footprint "eagle-import:MSOP8")
      (libsource (lib "eagle-import") (part "AD8132MSOP8"))
    )
    (comp (ref "U5")
      (value "AD8132MSOP8")
      (footprint "eagle-import:MSOP8")
      (libsource (lib "eagle-import") (part "AD8132MSOP8"))
    )
    (comp (ref "U6")
      (value "AD8132MSOP8")
      (footprint "eagle-import:MSOP8")
      (libsource (lib "eagle-import") (part "AD8132MSOP8"))
    )
    (comp (ref "U7")
      (value "AD8132MSOP8")
      (footprint "eagle-import:MSOP8")
      (libsource (lib "eagle-import") (part "AD8132MSOP8"))
    )
    (comp (ref "X4")
      (value "SMA-SMD")
      (footprint "eagle-import:SMA-SMD")
      (libsource (lib "eagle-import") (part "SMA-SMD"))
    )
    (comp (ref "X5")
      (value "SMA-SMD")
      (footprint "eagle-import:SMA-SMD")
      (libsource (lib "eagle-import") (part "SMA-SMD"))
    )
    (comp (ref "X6")
      (value "SMA-SMD")
      (footprint "eagle-import:SMA-SMD")
      (libsource (lib "eagle-import") (part "SMA-SMD"))
    )
    (comp (ref "X7")
      (value "SMA-SMD")
      (footprint "eagle-import:SMA-SMD")
      (libsource (lib "eagle-import") (part "SMA-SMD"))
    )
  )
  (nets
    (net (code "1") (name "A0") (class "Default")
      (node (ref "IC1") (pin "1") (pinfunction "A0_1") (pintype "input"))
      (node (ref "RA00") (pin "2") (pinfunction "2_2") (pintype "passive"))
      (node (ref "RA01") (pin "2") (pinfunction "2_2") (pintype "passive"))
    )
    (net (code "2") (name "A1") (class "Default")
      (node (ref "IC1") (pin "2") (pinfunction "A1_2") (pintype "input"))
      (node (ref "RA10") (pin "2") (pinfunction "2_2") (pintype "passive"))
      (node (ref "RA11") (pin "2") (pinfunction "2_2") (pintype "passive"))
    )
    (net (code "3") (name "A1V5") (class "Default")
      (node (ref "J1") (pin "79") (pinfunction "79_79") (pintype "passive"))
      (node (ref "J1") (pin "80") (pinfunction "80_80") (pintype "passive"))
    )
    (net (code "4") (name "A2") (class "Default")
      (node (ref "IC1") (pin "3") (pinfunction "A2_3") (pintype "input"))
      (node (ref "RA20") (pin "2") (pinfunction "2_2") (pintype "passive"))
      (node (ref "RA21") (pin "2") (pinfunction "2_2") (pintype "passive"))
    )
    (net (code "5") (name "A3V3") (class "Default")
      (node (ref "J1") (pin "81") (pinfunction "81_81") (pintype "passive"))
      (node (ref "J1") (pin "82") (pinfunction "82_82") (pintype "passive"))
      (node (ref "R8") (pin "1") (pinfunction "1_1") (pintype "passive"))
      (node (ref "R9") (pin "1") (pinfunction "1_1") (pintype "passive"))
    )
    (net (code "6") (name "A3V3_BB") (class "Default")
      (node (ref "C41") (pin "+") (pinfunction "+_+") (pintype "passive"))
      (node (ref "C42") (pin "1") (pinfunction "1_1") (pintype "passive"))
      (node (ref "C43") (pin "1") (pinfunction "1_1") (pintype "passive"))
      (node (ref "C51") (pin "+") (pinfunction "+_+") (pintype "passive"))
      (node (ref "C52") (pin "1") (pinfunction "1_1") (pintype "passive"))
      (node (ref "C53") (pin "1") (pinfunction "1_1") (pintype "passive"))
      (node (ref "C61") (pin "+") (pinfunction "+_+") (pintype "passive"))
      (node (ref "C62") (pin "1") (pinfunction "1_1") (pintype "passive"))
      (node (ref "C63") (pin "1") (pinfunction "1_1") (pintype "passive"))
      (node (ref "C71") (pin "+") (pinfunction "+_+") (pintype "passive"))
      (node (ref "C72") (pin "1") (pinfunction "1_1") (pintype "passive"))
      (node (ref "C73") (pin "1") (pinfunction "1_1") (pintype "passive"))
      (node (ref "R451") (pin "2") (pinfunction "2_2") (pintype "passive"))
      (node (ref "R671") (pin "2") (pinfunction "2_2") (pintype "passive"))
      (node (ref "R8") (pin "2") (pinfunction "2_2") (pintype "passive"))
      (node (ref "U4") (pin "3") (pinfunction "V_S+_3") (pintype "power_in"))
      (node (ref "U5") (pin "3") (pinfunction "V_S+_3") (pintype "power_in"))
      (node (ref "U6") (pin "3") (pinfunction "V_S+_3") (pintype "power_in"))
      (node (ref "U7") (pin "3") (pinfunction "V_S+_3") (pintype "power_in"))
    )
    (net (code "7") (name "A3V3_RF") (class "Default")
      (node (ref "C101") (pin "+") (pinfunction "+_+") (pintype "passive"))
      (node (ref "C102") (pin "1") (pinfunction "1_1") (pintype "passive"))
      (node (ref "C103") (pin "1") (pinfunction "1_1") (pintype "passive"))
      (node (ref "C104") (pin "1") (pinfunction "1_1") (pintype "passive"))
      (node (ref "C105") (pin "2") (pinfunction "2_2") (pintype "passive"))
      (node (ref "C106") (pin "2") (pinfunction "2_2") (pintype "passive"))
      (node (ref "C107") (pin "1") (pinfunction "1_1") (pintype "passive"))
      (node (ref "C108") (pin "1") (pinfunction "1_1") (pintype "passive"))
      (node (ref "C109") (pin "1") (pinfunction "1_1") (pintype "passive"))
      (node (ref "C110") (pin "1") (pinfunction "1_1") (pintype "passive"))
      (node (ref "C111") (pin "1") (pinfunction "1_1") (pintype "passive"))
      (node (ref "C112") (pin "1") (pinfunction "1_1") (pintype "passive"))
      (node (ref "C113") (pin "1") (pinfunction "1_1") (pintype "passive"))
      (node (ref "C114") (pin "1") (pinfunction "1_1") (pintype "passive"))
      (node (ref "C115") (pin "1") (pinfunction "1_1") (pintype "passive"))
      (node (ref "C116") (pin "1") (pinfunction "1_1") (pintype "passive"))
      (node (ref "R9") (pin "2") (pinfunction "2_2") (pintype "passive"))
      (node (ref "U1") (pin "1") (pinfunction "VCCLNA_1") (pintype "power_in"))
      (node (ref "U1") (pin "13") (pinfunction "VCCTXPA_13") (pintype "power_in"))
      (node (ref "U1") (pin "17") (pinfunction "VCCTXMX_17") (pintype "power_in"))
      (node (ref "U1") (pin "20") (pinfunction "VCCPLL_20") (pintype "power_in"))
      (node (ref "U1") (pin "25") (pinfunction "VCCCP_25") (pintype "power_in"))
      (node (ref "U1") (pin "27") (pinfunction "VCCXTAL_27") (pintype "power_in"))
      (node (ref "U1") (pin "30") (pinfunction "VCCVCO_30") (pintype "power_in"))
      (node (ref "U1") (pin "39") (pinfunction "VCCRXVGA_39") (pintype "power_in"))
      (node (ref "U1") (pin "41") (pinfunction "VCCRXFL_41") (pintype "power_in"))
      (node (ref "U1") (pin "46") (pinfunction "VCCRXMX_46") (pintype "power_in"))
      (node (ref "U1") (pin "7") (pinfunction "VCCPA_7") (pintype "power_in"))
    )
    (net (code "8") (name "ADC3+") (class "Default")
      (node (ref "J1") (pin "70") (pinfunction "70_70") (pintype "passive"))
      (node (ref "R47") (pin "2") (pinfunction "2_2") (pintype "passive"))
    )
    (net (code "9") (name "ADC3-") (class "Default")
      (node (ref "J1") (pin "68") (pinfunction "68_68") (pintype "passive"))
      (node (ref "R48") (pin "2") (pinfunction "2_2") (pintype "passive"))
    )
    (net (code "10") (name "ADC4+") (class "Default")
      (node (ref "J1") (pin "76") (pinfunction "76_76") (pintype "passive"))
      (node (ref "R57") (pin "2") (pinfunction "2_2") (pintype "passive"))
    )
    (net (code "11") (name "ADC4-") (class "Default")
      (node (ref "J1") (pin "74") (pinfunction "74_74") (pintype "passive"))
      (node (ref "R58") (pin "2") (pinfunction "2_2") (pintype "passive"))
    )
    (net (code "12") (name "AGND") (class "Default")
      (node (ref "C101") (pin "-") (pinfunction "-_-") (pintype "passive"))
      (node (ref "C102") (pin "2") (pinfunction "2_2") (pintype "passive"))
      (node (ref "C103") (pin "2") (pinfunction "2_2") (pintype "passive"))
      (node (ref "C104") (pin "2") (pinfunction "2_2") (pintype "passive"))
      (node (ref "C105") (pin "1") (pinfunction "1_1") (pintype "passive"))
      (node (ref "C106") (pin "1") (pinfunction "1_1") (pintype "passive"))
      (node (ref "C107") (pin "2") (pinfunction "2_2") (pintype "passive"))
      (node (ref "C108") (pin "2") (pinfunction "2_2") (pintype "passive"))
      (node (ref "C109") (pin "2") (pinfunction "2_2") (pintype "passive"))
      (node (ref "C110") (pin "2") (pinfunction "2_2") (pintype "passive"))
      (node (ref "C111") (pin "2") (pinfunction "2_2") (pintype "passive"))
      (node (ref "C112") (pin "2") (pinfunction "2_2") (pintype "passive"))
      (node (ref "C113") (pin "2") (pinfunction "2_2") (pintype "passive"))
      (node (ref "C114") (pin "2") (pinfunction "2_2") (pintype "passive"))
      (node (ref "C115") (pin "2") (pinfunction "2_2") (pintype "passive"))
      (node (ref "C116") (pin "2") (pinfunction "2_2") (pintype "passive"))
      (node (ref "C117") (pin "2") (pinfunction "2_2") (pintype "passive"))
      (node (ref "C118") (pin "2") (pinfunction "2_2") (pintype "passive"))
      (node (ref "C119") (pin "2") (pinfunction "2_2") (pintype "passive"))
      (node (ref "C120") (pin "2") (pinfunction "2_2") (pintype "passive"))
      (node (ref "C41") (pin "-") (pinfunction "-_-") (pintype "passive"))
      (node (ref "C42") (pin "2") (pinfunction "2_2") (pintype "passive"))
      (node (ref "C43") (pin "2") (pinfunction "2_2") (pintype "passive"))
      (node (ref "C45") (pin "2") (pinfunction "2_2") (pintype "passive"))
      (node (ref "C51") (pin "-") (pinfunction "-_-") (pintype "passive"))
      (node (ref "C52") (pin "2") (pinfunction "2_2") (pintype "passive"))
      (node (ref "C53") (pin "2") (pinfunction "2_2") (pintype "passive"))
      (node (ref "C61") (pin "-") (pinfunction "-_-") (pintype "passive"))
      (node (ref "C62") (pin "2") (pinfunction "2_2") (pintype "passive"))
      (node (ref "C63") (pin "2") (pinfunction "2_2") (pintype "passive"))
      (node (ref "C64") (pin "2") (pinfunction "2_2") (pintype "passive"))
      (node (ref "C67") (pin "2") (pinfunction "2_2") (pintype "passive"))
      (node (ref "C71") (pin "-") (pinfunction "-_-") (pintype "passive"))
      (node (ref "C72") (pin "2") (pinfunction "2_2") (pintype "passive"))
      (node (ref "C73") (pin "2") (pinfunction "2_2") (pintype "passive"))
      (node (ref "C74") (pin "2") (pinfunction "2_2") (pintype "passive"))
      (node (ref "J1") (pin "29") (pinfunction "29_29") (pintype "passive"))
      (node (ref "J1") (pin "30") (pinfunction "30_30") (pintype "passive"))
      (node (ref "J1") (pin "35") (pinfunction "35_35") (pintype "passive"))
      (node (ref "J1") (pin "36") (pinfunction "36_36") (pintype "passive"))
      (node (ref "J1") (pin "41") (pinfunction "41_41") (pintype "passive"))
      (node (ref "J1") (pin "42") (pinfunction "42_42") (pintype "passive"))
      (node (ref "J1") (pin "47") (pinfunction "47_47") (pintype "passive"))
      (node (ref "J1") (pin "48") (pinfunction "48_48") (pintype "passive"))
      (node (ref "J1") (pin "53") (pinfunction "53_53") (pintype "passive"))
      (node (ref "J1") (pin "54") (pinfunction "54_54") (pintype "passive"))
      (node (ref "J1") (pin "59") (pinfunction "59_59") (pintype "passive"))
      (node (ref "J1") (pin "60") (pinfunction "60_60") (pintype "passive"))
      (node (ref "J1") (pin "65") (pinfunction "65_65") (pintype "passive"))
      (node (ref "J1") (pin "66") (pinfunction "66_66") (pintype "passive"))
      (node (ref "J1") (pin "71") (pinfunction "71_71") (pintype "passive"))
      (node (ref "J1") (pin "72") (pinfunction "72_72") (pintype "passive"))
      (node (ref "J1") (pin "77") (pinfunction "77_77") (pintype "passive"))
      (node (ref "J1") (pin "78") (pinfunction "78_78") (pintype "passive"))
      (node (ref "J1") (pin "83") (pinfunction "83_83") (pintype "passive"))
      (node (ref "J1") (pin "84") (pinfunction "84_84") (pintype "passive"))
      (node (ref "R4") (pin "2") (pinfunction "2_2") (pintype "passive"))
      (node (ref "R41") (pin "1") (pinfunction "1_1") (pintype "passive"))
      (node (ref "R42") (pin "1") (pinfunction "1_1") (pintype "passive"))
      (node (ref "R452") (pin "1") (pinfunction "1_1") (pintype "passive"))
      (node (ref "R51") (pin "1") (pinfunction "1_1") (pintype "passive"))
      (node (ref "R52") (pin "1") (pinfunction "1_1") (pintype "passive"))
      (node (ref "R672") (pin "1") (pinfunction "1_1") (pintype "passive"))
      (node (ref "U1") (pin "2") (pinfunction "GNDRXLNA_2") (pintype "power_in"))
      (node (ref "U1") (pin "26") (pinfunction "GNDCP_26") (pintype "power_in"))
      (node (ref "U1") (pin "31") (pinfunction "GNDVCO_31") (pintype "power_in"))
      (node (ref "U1") (pin "49") (pinfunction "EP_49") (pintype "power_in"))
      (node (ref "U2") (pin "2") (pinfunction "2_2") (pintype "power_in"))
      (node (ref "U2") (pin "5") (pinfunction "5_5") (pintype "power_in"))
      (node (ref "U3") (pin "2") (pinfunction "2_2") (pintype "power_in"))
      (node (ref "U3") (pin "5") (pinfunction "5_5") (pintype "power_in"))
      (node (ref "U4") (pin "6") (pinfunction "V_S-_6") (pintype "power_in"))
      (node (ref "U5") (pin "6") (pinfunction "V_S-_6") (pintype "power_in"))
      (node (ref "U6") (pin "6") (pinfunction "V_S-_6") (pintype "power_in"))
      (node (ref "U7") (pin "6") (pinfunction "V_S-_6") (pintype "power_in"))
      (node (ref "X1") (pin "2@1") (pinfunction "GND_2@1") (pintype "power_in"))
      (node (ref "X1") (pin "2@2") (pinfunction "GND_2@2") (pintype "power_in"))
      (node (ref "X1") (pin "2@3") (pinfunction "GND_2@3") (pintype "power_in"))
      (node (ref "X1") (pin "2@4") (pinfunction "GND_2@4") (pintype "power_in"))
      (node (ref "X1") (pin "2@5") (pinfunction "GND_2@5") (pintype "power_in"))
      (node (ref "X1") (pin "2@6") (pinfunction "GND_2@6") (pintype "power_in"))
      (node (ref "X2") (pin "2@1") (pinfunction "GND_2@1") (pintype "power_in"))
      (node (ref "X2") (pin "2@2") (pinfunction "GND_2@2") (pintype "power_in"))
      (node (ref "X2") (pin "2@3") (pinfunction "GND_2@3") (pintype "power_in"))
      (node (ref "X2") (pin "2@4") (pinfunction "GND_2@4") (pintype "power_in"))
      (node (ref "X2") (pin "2@5") (pinfunction "GND_2@5") (pintype "power_in"))
      (node (ref "X2") (pin "2@6") (pinfunction "GND_2@6") (pintype "power_in"))
      (node (ref "X4") (pin "2@1") (pinfunction "GND_2@1") (pintype "power_in"))
      (node (ref "X4") (pin "2@2") (pinfunction "GND_2@2") (pintype "power_in"))
      (node (ref "X4") (pin "2@3") (pinfunction "GND_2@3") (pintype "power_in"))
      (node (ref "X4") (pin "2@4") (pinfunction "GND_2@4") (pintype "power_in"))
      (node (ref "X4") (pin "2@5") (pinfunction "GND_2@5") (pintype "power_in"))
      (node (ref "X4") (pin "2@6") (pinfunction "GND_2@6") (pintype "power_in"))
      (node (ref "X5") (pin "2@1") (pinfunction "GND_2@1") (pintype "power_in"))
      (node (ref "X5") (pin "2@2") (pinfunction "GND_2@2") (pintype "power_in"))
      (node (ref "X5") (pin "2@3") (pinfunction "GND_2@3") (pintype "power_in"))
      (node (ref "X5") (pin "2@4") (pinfunction "GND_2@4") (pintype "power_in"))
      (node (ref "X5") (pin "2@5") (pinfunction "GND_2@5") (pintype "power_in"))
      (node (ref "X5") (pin "2@6") (pinfunction "GND_2@6") (pintype "power_in"))
      (node (ref "X6") (pin "2@1") (pinfunction "GND_2@1") (pintype "power_in"))
      (node (ref "X6") (pin "2@2") (pinfunction "GND_2@2") (pintype "power_in"))
      (node (ref "X6") (pin "2@3") (pinfunction "GND_2@3") (pintype "power_in"))
      (node (ref "X6") (pin "2@4") (pinfunction "GND_2@4") (pintype "power_in"))
      (node (ref "X6") (pin "2@5") (pinfunction "GND_2@5") (pintype "power_in"))
      (node (ref "X6") (pin "2@6") (pinfunction "GND_2@6") (pintype "power_in"))
      (node (ref "X7") (pin "2@1") (pinfunction "GND_2@1") (pintype "power_in"))
      (node (ref "X7") (pin "2@2") (pinfunction "GND_2@2") (pintype "power_in"))
      (node (ref "X7") (pin "2@3") (pinfunction "GND_2@3") (pintype "power_in"))
      (node (ref "X7") (pin "2@4") (pinfunction "GND_2@4") (pintype "power_in"))
      (node (ref "X7") (pin "2@5") (pinfunction "GND_2@5") (pintype "power_in"))
      (node (ref "X7") (pin "2@6") (pinfunction "GND_2@6") (pintype "power_in"))
    )
    (net (code "13") (name "ANTSEL") (class "Default")
      (node (ref "SW2") (pin "2") (pinfunction "2_2") (pintype "passive"))
      (node (ref "U1") (pin "47") (pinfunction "ANTSEL_47") (pintype "input"))
    )
    (net (code "14") (name "B1") (class "Default")
      (node (ref "J1") (pin "11") (pinfunction "11_11") (pintype "passive"))
      (node (ref "U1") (pin "23") (pinfunction "B1_23") (pintype "input"))
    )
    (net (code "15") (name "B2") (class "Default")
      (node (ref "J1") (pin "19") (pinfunction "19_19") (pintype "passive"))
      (node (ref "U1") (pin "11") (pinfunction "B2_11") (pintype "input"))
    )
    (net (code "16") (name "B3") (class "Default")
      (node (ref "J1") (pin "21") (pinfunction "21_21") (pintype "passive"))
      (node (ref "U1") (pin "8") (pinfunction "B3_8") (pintype "input"))
    )
    (net (code "17") (name "B4") (class "Default")
      (node (ref "J1") (pin "15") (pinfunction "15_15") (pintype "passive"))
      (node (ref "U1") (pin "34") (pinfunction "B4_34") (pintype "input"))
    )
    (net (code "18") (name "B5") (class "Default")
      (node (ref "J1") (pin "16") (pinfunction "16_16") (pintype "passive"))
      (node (ref "U1") (pin "14") (pinfunction "B5_14") (pintype "input"))
    )
    (net (code "19") (name "B6") (class "Default")
      (node (ref "SW3") (pin "2") (pinfunction "2_2") (pintype "passive"))
      (node (ref "U1") (pin "3") (pinfunction "B6_3") (pintype "input"))
    )
    (net (code "20") (name "B7") (class "Default")
      (node (ref "SW4") (pin "2") (pinfunction "2_2") (pintype "passive"))
      (node (ref "U1") (pin "6") (pinfunction "B7_6") (pintype "input"))
    )
    (net (code "21") (name "BYPASS") (class "Default")
      (node (ref "C117") (pin "1") (pinfunction "1_1") (pintype "passive"))
      (node (ref "U1") (pin "33") (pinfunction "BYPASS_33") (pintype "power_in"))
    )
    (net (code "22") (name "CLK1") (class "Default")
      (node (ref "J1") (pin "12") (pinfunction "12_12") (pintype "passive"))
      (node (ref "X8") (pin "1") (pinfunction "1_1") (pintype "passive"))
    )
    (net (code "23") (name "CLK2") (class "Default")
      (node (ref "J1") (pin "14") (pinfunction "14_14") (pintype "passive"))
      (node (ref "R5") (pin "1") (pinfunction "1_1") (pintype "passive"))
      (node (ref "R6") (pin "1") (pinfunction "1_1") (pintype "passive"))
    )
    (net (code "24") (name "D1V5") (class "Default")
      (node (ref "J1") (pin "7") (pinfunction "7_7") (pintype "passive"))
      (node (ref "J1") (pin "8") (pinfunction "8_8") (pintype "passive"))
    )
    (net (code "25") (name "D3V3") (class "Default")
      (node (ref "IC1") (pin "8") (pinfunction "VCC_8") (pintype "power_in"))
      (node (ref "J1") (pin "5") (pinfunction "5_5") (pintype "passive"))
      (node (ref "J1") (pin "6") (pinfunction "6_6") (pintype "passive"))
      (node (ref "R1") (pin "2") (pinfunction "2_2") (pintype "passive"))
      (node (ref "R2") (pin "2") (pinfunction "2_2") (pintype "passive"))
      (node (ref "R7") (pin "2") (pinfunction "2_2") (pintype "passive"))
      (node (ref "RA01") (pin "1") (pinfunction "1_1") (pintype "passive"))
      (node (ref "RA11") (pin "1") (pinfunction "1_1") (pintype "passive"))
      (node (ref "RA21") (pin "1") (pinfunction "1_1") (pintype "passive"))
      (node (ref "RWP1") (pin "1") (pinfunction "1_1") (pintype "passive"))
      (node (ref "SW1") (pin "1") (pinfunction "1_1") (pintype "passive"))
      (node (ref "SW2") (pin "1") (pinfunction "1_1") (pintype "passive"))
      (node (ref "SW3") (pin "1") (pinfunction "1_1") (pintype "passive"))
      (node (ref "SW4") (pin "1") (pinfunction "1_1") (pintype "passive"))
    )
    (net (code "26") (name "DAC3+") (class "Default")
      (node (ref "J1") (pin "58") (pinfunction "58_58") (pintype "passive"))
      (node (ref "R62") (pin "1") (pinfunction "1_1") (pintype "passive"))
    )
    (net (code "27") (name "DAC3-") (class "Default")
      (node (ref "J1") (pin "56") (pinfunction "56_56") (pintype "passive"))
      (node (ref "R61") (pin "1") (pinfunction "1_1") (pintype "passive"))
    )
    (net (code "28") (name "DAC4+") (class "Default")
      (node (ref "J1") (pin "64") (pinfunction "64_64") (pintype "passive"))
      (node (ref "R72") (pin "1") (pinfunction "1_1") (pintype "passive"))
    )
    (net (code "29") (name "DAC4-") (class "Default")
      (node (ref "J1") (pin "62") (pinfunction "62_62") (pintype "passive"))
      (node (ref "R71") (pin "1") (pinfunction "1_1") (pintype "passive"))
    )
    (net (code "30") (name "DGND") (class "Default")
      (node (ref "C123") (pin "2") (pinfunction "2_2") (pintype "passive"))
      (node (ref "C124") (pin "2") (pinfunction "2_2") (pintype "passive"))
      (node (ref "C125") (pin "2") (pinfunction "2_2") (pintype "passive"))
      (node (ref "C126") (pin "1") (pinfunction "1_1") (pintype "passive"))
      (node (ref "IC1") (pin "4") (pinfunction "GND_4") (pintype "power_in"))
      (node (ref "J1") (pin "1") (pinfunction "1_1") (pintype "passive"))
      (node (ref "J1") (pin "10") (pinfunction "10_10") (pintype "passive"))
      (node (ref "J1") (pin "2") (pinfunction "2_2") (pintype "passive"))
      (node (ref "J1") (pin "9") (pinfunction "9_9") (pintype "passive"))
      (node (ref "R4") (pin "1") (pinfunction "1_1") (pintype "passive"))
      (node (ref "RA00") (pin "1") (pinfunction "1_1") (pintype "passive"))
      (node (ref "RA10") (pin "1") (pinfunction "1_1") (pintype "passive"))
      (node (ref "RA20") (pin "1") (pinfunction "1_1") (pintype "passive"))
      (node (ref "RWP0") (pin "1") (pinfunction "1_1") (pintype "passive"))
      (node (ref "SW1") (pin "3") (pinfunction "3_3") (pintype "passive"))
      (node (ref "SW2") (pin "3") (pinfunction "3_3") (pintype "passive"))
      (node (ref "SW3") (pin "3") (pinfunction "3_3") (pintype "passive"))
      (node (ref "SW4") (pin "3") (pinfunction "3_3") (pintype "passive"))
      (node (ref "X3") (pin "2") (pinfunction "GND_2") (pintype "power_in"))
      (node (ref "X8") (pin "2@1") (pinfunction "GND_2@1") (pintype "power_in"))
      (node (ref "X8") (pin "2@2") (pinfunction "GND_2@2") (pintype "power_in"))
      (node (ref "X8") (pin "2@3") (pinfunction "GND_2@3") (pintype "power_in"))
      (node (ref "X8") (pin "2@4") (pinfunction "GND_2@4") (pintype "power_in"))
      (node (ref "X8") (pin "2@5") (pinfunction "GND_2@5") (pintype "power_in"))
      (node (ref "X8") (pin "2@6") (pinfunction "GND_2@6") (pintype "power_in"))
      (node (ref "X9") (pin "1") (pinfunction "1_1") (pintype "passive"))
      (node (ref "X9") (pin "2") (pinfunction "2_2") (pintype "power_in"))
      (node (ref "X9") (pin "4") (pinfunction "4_4") (pintype "power_in"))
    )
    (net (code "31") (name "DIN") (class "Default")
      (node (ref "J1") (pin "20") (pinfunction "20_20") (pintype "passive"))
      (node (ref "U1") (pin "19") (pinfunction "DIN_19") (pintype "input"))
    )
    (net (code "32") (name "I2C_SCL") (class "Default")
      (node (ref "IC1") (pin "6") (pinfunction "SCL_6") (pintype "input"))
      (node (ref "J1") (pin "26") (pinfunction "26_26") (pintype "passive"))
      (node (ref "R1") (pin "1") (pinfunction "1_1") (pintype "passive"))
    )
    (net (code "33") (name "I2C_SDA") (class "Default")
      (node (ref "IC1") (pin "5") (pinfunction "SDA_5") (pintype "bidirectional"))
      (node (ref "J1") (pin "28") (pinfunction "28_28") (pintype "passive"))
      (node (ref "R2") (pin "1") (pinfunction "1_1") (pintype "passive"))
    )
    (net (code "34") (name "LD") (class "Default")
      (node (ref "J1") (pin "13") (pinfunction "13_13") (pintype "passive"))
      (node (ref "U1") (pin "22") (pinfunction "LD_22") (pintype "output"))
    )
    (net (code "35") (name "Net-(C64-Pad1)") (class "Default")
      (node (ref "C64") (pin "1") (pinfunction "1_1") (pintype "passive"))
      (node (ref "R65") (pin "2") (pinfunction "2_2") (pintype "passive"))
      (node (ref "R66") (pin "1") (pinfunction "1_1") (pintype "passive"))
    )
    (net (code "36") (name "Net-(C74-Pad1)") (class "Default")
      (node (ref "C74") (pin "1") (pinfunction "1_1") (pintype "passive"))
      (node (ref "R75") (pin "2") (pinfunction "2_2") (pintype "passive"))
      (node (ref "R76") (pin "1") (pinfunction "1_1") (pintype "passive"))
    )
    (net (code "37") (name "Net-(C119-Pad1)") (class "Default")
      (node (ref "C119") (pin "1") (pinfunction "1_1") (pintype "passive"))
      (node (ref "R102") (pin "2") (pinfunction "2_2") (pintype "passive"))
    )
    (net (code "38") (name "Net-(C128-Pad1)") (class "Default")
      (node (ref "C128") (pin "1") (pinfunction "1_1") (pintype "passive"))
      (node (ref "X9") (pin "3") (pinfunction "3_3") (pintype "passive"))
    )
    (net (code "39") (name "Net-(R41-Pad2)") (class "Default")
      (node (ref "R41") (pin "2") (pinfunction "2_2") (pintype "passive"))
      (node (ref "R43") (pin "1") (pinfunction "1_1") (pintype "passive"))
      (node (ref "X4") (pin "1") (pinfunction "1_1") (pintype "passive"))
    )
    (net (code "40") (name "Net-(R42-Pad2)") (class "Default")
      (node (ref "R42") (pin "2") (pinfunction "2_2") (pintype "passive"))
      (node (ref "R44") (pin "1") (pinfunction "1_1") (pintype "passive"))
    )
    (net (code "41") (name "Net-(R51-Pad2)") (class "Default")
      (node (ref "R51") (pin "2") (pinfunction "2_2") (pintype "passive"))
      (node (ref "R53") (pin "1") (pinfunction "1_1") (pintype "passive"))
      (node (ref "X5") (pin "1") (pinfunction "1_1") (pintype "passive"))
    )
    (net (code "42") (name "Net-(R52-Pad2)") (class "Default")
      (node (ref "R52") (pin "2") (pinfunction "2_2") (pintype "passive"))
      (node (ref "R54") (pin "1") (pinfunction "1_1") (pintype "passive"))
    )
    (net (code "43") (name "Net-(R66-Pad2)") (class "Default")
      (node (ref "R66") (pin "2") (pinfunction "2_2") (pintype "passive"))
      (node (ref "X6") (pin "1") (pinfunction "1_1") (pintype "passive"))
    )
    (net (code "44") (name "Net-(R76-Pad2)") (class "Default")
      (node (ref "R76") (pin "2") (pinfunction "2_2") (pintype "passive"))
      (node (ref "X7") (pin "1") (pinfunction "1_1") (pintype "passive"))
    )
    (net (code "45") (name "Net-(U1A-ANT1+)") (class "Default")
      (node (ref "U1") (pin "4") (pinfunction "ANT1+_4") (pintype "bidirectional"))
      (node (ref "U2") (pin "4") (pinfunction "4_4") (pintype "bidirectional"))
    )
    (net (code "46") (name "Net-(U1A-ANT1-)") (class "Default")
      (node (ref "U1") (pin "5") (pinfunction "ANT1-_5") (pintype "bidirectional"))
      (node (ref "U2") (pin "3") (pinfunction "3_3") (pintype "bidirectional"))
    )
    (net (code "47") (name "Net-(U1A-ANT2+)") (class "Default")
      (node (ref "U1") (pin "9") (pinfunction "ANT2+_9") (pintype "bidirectional"))
      (node (ref "U3") (pin "4") (pinfunction "4_4") (pintype "bidirectional"))
    )
    (net (code "48") (name "Net-(U1A-ANT2-)") (class "Default")
      (node (ref "U1") (pin "10") (pinfunction "ANT2-_10") (pintype "bidirectional"))
      (node (ref "U3") (pin "3") (pinfunction "3_3") (pintype "bidirectional"))
    )
    (net (code "49") (name "Net-(U1D-CLOCKOUT)") (class "Default")
      (node (ref "R5") (pin "2") (pinfunction "2_2") (pintype "passive"))
      (node (ref "U1") (pin "21") (pinfunction "CLOCKOUT_21") (pintype "output"))
    )
    (net (code "50") (name "Net-(U1D-CPOUT)") (class "Default")
      (node (ref "C120") (pin "1") (pinfunction "1_1") (pintype "passive"))
      (node (ref "R101") (pin "1") (pinfunction "1_1") (pintype "passive"))
      (node (ref "R102") (pin "1") (pinfunction "1_1") (pintype "passive"))
      (node (ref "U1") (pin "24") (pinfunction "CPOUT_24") (pintype "output"))
    )
    (net (code "51") (name "Net-(U1D-CTUNE)") (class "Default")
      (node (ref "C126") (pin "2") (pinfunction "2_2") (pintype "passive"))
      (node (ref "C127") (pin "1") (pinfunction "1_1") (pintype "passive"))
      (node (ref "U1") (pin "29") (pinfunction "CTUNE_29") (pintype "input"))
    )
    (net (code "52") (name "Net-(U1D-TUNE)") (class "Default")
      (node (ref "C118") (pin "1") (pinfunction "1_1") (pintype "passive"))
      (node (ref "R101") (pin "2") (pinfunction "2_2") (pintype "passive"))
      (node (ref "U1") (pin "32") (pinfunction "TUNE_32") (pintype "input"))
    )
    (net (code "53") (name "Net-(U1D-XTAL)") (class "Default")
      (node (ref "C121") (pin "1") (pinfunction "1_1") (pintype "passive"))
      (node (ref "C127") (pin "2") (pinfunction "2_2") (pintype "passive"))
      (node (ref "C128") (pin "2") (pinfunction "2_2") (pintype "passive"))
      (node (ref "U1") (pin "28") (pinfunction "XTAL_28") (pintype "input"))
    )
    (net (code "54") (name "Net-(U2-Pad1)") (class "Default")
      (node (ref "U2") (pin "1") (pinfunction "1_1") (pintype "bidirectional"))
      (node (ref "X1") (pin "1") (pinfunction "1_1") (pintype "passive"))
    )
    (net (code "55") (name "Net-(U3-Pad1)") (class "Default")
      (node (ref "U3") (pin "1") (pinfunction "1_1") (pintype "bidirectional"))
      (node (ref "X2") (pin "1") (pinfunction "1_1") (pintype "passive"))
    )
    (net (code "56") (name "Net-(U4-+IN)") (class "Default")
      (node (ref "R43") (pin "2") (pinfunction "2_2") (pintype "passive"))
      (node (ref "R45") (pin "1") (pinfunction "1_1") (pintype "passive"))
      (node (ref "U4") (pin "8") (pinfunction "+IN_8") (pintype "input"))
    )
    (net (code "57") (name "Net-(U4-+OUT)") (class "Default")
      (node (ref "R46") (pin "2") (pinfunction "2_2") (pintype "passive"))
      (node (ref "R48") (pin "1") (pinfunction "1_1") (pintype "passive"))
      (node (ref "U4") (pin "4") (pinfunction "+OUT_4") (pintype "output"))
    )
    (net (code "58") (name "Net-(U4--IN)") (class "Default")
      (node (ref "R44") (pin "2") (pinfunction "2_2") (pintype "passive"))
      (node (ref "R46") (pin "1") (pinfunction "1_1") (pintype "passive"))
      (node (ref "U4") (pin "1") (pinfunction "-IN_1") (pintype "input"))
    )
    (net (code "59") (name "Net-(U4--OUT)") (class "Default")
      (node (ref "R45") (pin "2") (pinfunction "2_2") (pintype "passive"))
      (node (ref "R47") (pin "1") (pinfunction "1_1") (pintype "passive"))
      (node (ref "U4") (pin "5") (pinfunction "-OUT_5") (pintype "output"))
    )
    (net (code "60") (name "Net-(U5-+IN)") (class "Default")
      (node (ref "R53") (pin "2") (pinfunction "2_2") (pintype "passive"))
      (node (ref "R55") (pin "1") (pinfunction "1_1") (pintype "passive"))
      (node (ref "U5") (pin "8") (pinfunction "+IN_8") (pintype "input"))
    )
    (net (code "61") (name "Net-(U5-+OUT)") (class "Default")
      (node (ref "R56") (pin "2") (pinfunction "2_2") (pintype "passive"))
      (node (ref "R58") (pin "1") (pinfunction "1_1") (pintype "passive"))
      (node (ref "U5") (pin "4") (pinfunction "+OUT_4") (pintype "output"))
    )
    (net (code "62") (name "Net-(U5--IN)") (class "Default")
      (node (ref "R54") (pin "2") (pinfunction "2_2") (pintype "passive"))
      (node (ref "R56") (pin "1") (pinfunction "1_1") (pintype "passive"))
      (node (ref "U5") (pin "1") (pinfunction "-IN_1") (pintype "input"))
    )
    (net (code "63") (name "Net-(U5--OUT)") (class "Default")
      (node (ref "R55") (pin "2") (pinfunction "2_2") (pintype "passive"))
      (node (ref "R57") (pin "1") (pinfunction "1_1") (pintype "passive"))
      (node (ref "U5") (pin "5") (pinfunction "-OUT_5") (pintype "output"))
    )
    (net (code "64") (name "Net-(U6-+IN)") (class "Default")
      (node (ref "R61") (pin "2") (pinfunction "2_2") (pintype "passive"))
      (node (ref "R63") (pin "1") (pinfunction "1_1") (pintype "passive"))
      (node (ref "U6") (pin "8") (pinfunction "+IN_8") (pintype "input"))
    )
    (net (code "65") (name "Net-(U6-+OUT)") (class "Default")
      (node (ref "R64") (pin "2") (pinfunction "2_2") (pintype "passive"))
      (node (ref "U6") (pin "4") (pinfunction "+OUT_4") (pintype "output"))
    )
    (net (code "66") (name "Net-(U6--IN)") (class "Default")
      (node (ref "R62") (pin "2") (pinfunction "2_2") (pintype "passive"))
      (node (ref "R64") (pin "1") (pinfunction "1_1") (pintype "passive"))
      (node (ref "U6") (pin "1") (pinfunction "-IN_1") (pintype "input"))
    )
    (net (code "67") (name "Net-(U6--OUT)") (class "Default")
      (node (ref "R63") (pin "2") (pinfunction "2_2") (pintype "passive"))
      (node (ref "R65") (pin "1") (pinfunction "1_1") (pintype "passive"))
      (node (ref "U6") (pin "5") (pinfunction "-OUT_5") (pintype "output"))
    )
    (net (code "68") (name "Net-(U7-+IN)") (class "Default")
      (node (ref "R71") (pin "2") (pinfunction "2_2") (pintype "passive"))
      (node (ref "R73") (pin "1") (pinfunction "1_1") (pintype "passive"))
      (node (ref "U7") (pin "8") (pinfunction "+IN_8") (pintype "input"))
    )
    (net (code "69") (name "Net-(U7-+OUT)") (class "Default")
      (node (ref "R74") (pin "2") (pinfunction "2_2") (pintype "passive"))
      (node (ref "U7") (pin "4") (pinfunction "+OUT_4") (pintype "output"))
    )
    (net (code "70") (name "Net-(U7--IN)") (class "Default")
      (node (ref "R72") (pin "2") (pinfunction "2_2") (pintype "passive"))
      (node (ref "R74") (pin "1") (pinfunction "1_1") (pintype "passive"))
      (node (ref "U7") (pin "1") (pinfunction "-IN_1") (pintype "input"))
    )
    (net (code "71") (name "Net-(U7--OUT)") (class "Default")
      (node (ref "R73") (pin "2") (pinfunction "2_2") (pintype "passive"))
      (node (ref "R75") (pin "1") (pinfunction "1_1") (pintype "passive"))
      (node (ref "U7") (pin "5") (pinfunction "-OUT_5") (pintype "output"))
    )
    (net (code "72") (name "Net-(X3-FO)") (class "Default")
      (node (ref "C121") (pin "2") (pinfunction "2_2") (pintype "passive"))
      (node (ref "R6") (pin "2") (pinfunction "2_2") (pintype "passive"))
      (node (ref "X3") (pin "3") (pinfunction "FO_3") (pintype "output"))
    )
    (net (code "73") (name "Net-(X3-VCC)") (class "Default")
      (node (ref "C123") (pin "1") (pinfunction "1_1") (pintype "passive"))
      (node (ref "C124") (pin "1") (pinfunction "1_1") (pintype "passive"))
      (node (ref "C125") (pin "1") (pinfunction "1_1") (pintype "passive"))
      (node (ref "R7") (pin "1") (pinfunction "1_1") (pintype "passive"))
      (node (ref "X3") (pin "4") (pinfunction "VCC_4") (pintype "power_in"))
    )
    (net (code "74") (name "RSSI") (class "Default")
      (node (ref "J1") (pin "39") (pinfunction "39_39") (pintype "passive"))
      (node (ref "U1") (pin "16") (pinfunction "RSSI_16") (pintype "output"))
    )
    (net (code "75") (name "RXBBI+") (class "Default")
      (node (ref "J1") (pin "52") (pinfunction "52_52") (pintype "passive"))
      (node (ref "U1") (pin "38") (pinfunction "RXBBI+_38") (pintype "output"))
    )
    (net (code "76") (name "RXBBI-") (class "Default")
      (node (ref "J1") (pin "50") (pinfunction "50_50") (pintype "passive"))
      (node (ref "U1") (pin "37") (pinfunction "RXBBI-_37") (pintype "output"))
    )
    (net (code "77") (name "RXBBQ+") (class "Default")
      (node (ref "J1") (pin "46") (pinfunction "46_46") (pintype "passive"))
      (node (ref "U1") (pin "36") (pinfunction "RXBBQ+_36") (pintype "output"))
    )
    (net (code "78") (name "RXBBQ-") (class "Default")
      (node (ref "J1") (pin "44") (pinfunction "44_44") (pintype "passive"))
      (node (ref "U1") (pin "35") (pinfunction "RXBBQ-_35") (pintype "output"))
    )
    (net (code "79") (name "RXHP") (class "Default")
      (node (ref "SW1") (pin "2") (pinfunction "2_2") (pintype "passive"))
      (node (ref "U1") (pin "40") (pinfunction "RXHP_40") (pintype "input"))
    )
    (net (code "80") (name "RXTX") (class "Default")
      (node (ref "J1") (pin "23") (pinfunction "23_23") (pintype "passive"))
      (node (ref "U1") (pin "48") (pinfunction "RXTX_48") (pintype "input"))
    )
    (net (code "81") (name "SCLK") (class "Default")
      (node (ref "J1") (pin "18") (pinfunction "18_18") (pintype "passive"))
      (node (ref "U1") (pin "18") (pinfunction "SCLK_18") (pintype "input"))
    )
    (net (code "82") (name "TXBBI+") (class "Default")
      (node (ref "J1") (pin "40") (pinfunction "40_40") (pintype "passive"))
      (node (ref "U1") (pin "45") (pinfunction "TXBBI+_45") (pintype "input"))
    )
    (net (code "83") (name "TXBBI-") (class "Default")
      (node (ref "J1") (pin "38") (pinfunction "38_38") (pintype "passive"))
      (node (ref "U1") (pin "44") (pinfunction "TXBBI-_44") (pintype "input"))
    )
    (net (code "84") (name "TXBBQ+") (class "Default")
      (node (ref "J1") (pin "34") (pinfunction "34_34") (pintype "passive"))
      (node (ref "U1") (pin "43") (pinfunction "TXBBQ+_43") (pintype "input"))
    )
    (net (code "85") (name "TXBBQ-") (class "Default")
      (node (ref "J1") (pin "32") (pinfunction "32_32") (pintype "passive"))
      (node (ref "U1") (pin "42") (pinfunction "TXBBQ-_42") (pintype "input"))
    )
    (net (code "86") (name "VSUP") (class "Default")
      (node (ref "J1") (pin "3") (pinfunction "3_3") (pintype "passive"))
      (node (ref "J1") (pin "4") (pinfunction "4_4") (pintype "passive"))
    )
    (net (code "87") (name "V_BIAS_ADC") (class "Default")
      (node (ref "C45") (pin "1") (pinfunction "1_1") (pintype "passive"))
      (node (ref "R451") (pin "1") (pinfunction "1_1") (pintype "passive"))
      (node (ref "R452") (pin "2") (pinfunction "2_2") (pintype "passive"))
      (node (ref "U4") (pin "2") (pinfunction "V_OCM_2") (pintype "input"))
      (node (ref "U5") (pin "2") (pinfunction "V_OCM_2") (pintype "input"))
    )
    (net (code "88") (name "V_BIAS_DAC") (class "Default")
      (node (ref "C67") (pin "1") (pinfunction "1_1") (pintype "passive"))
      (node (ref "R671") (pin "1") (pinfunction "1_1") (pintype "passive"))
      (node (ref "R672") (pin "2") (pinfunction "2_2") (pintype "passive"))
      (node (ref "U6") (pin "2") (pinfunction "V_OCM_2") (pintype "input"))
      (node (ref "U7") (pin "2") (pinfunction "V_OCM_2") (pintype "input"))
    )
    (net (code "89") (name "WP") (class "Default")
      (node (ref "IC1") (pin "7") (pinfunction "WP_7") (pintype "input"))
      (node (ref "RWP0") (pin "2") (pinfunction "2_2") (pintype "passive"))
      (node (ref "RWP1") (pin "2") (pinfunction "2_2") (pintype "passive"))
    )
    (net (code "90") (name "unconnected-(J1-Pad22)") (class "Default")
      (node (ref "J1") (pin "22") (pinfunction "22_22") (pintype "passive"))
    )
    (net (code "91") (name "unconnected-(J1-Pad25)") (class "Default")
      (node (ref "J1") (pin "25") (pinfunction "25_25") (pintype "passive"))
    )
    (net (code "92") (name "unconnected-(J1-Pad27)") (class "Default")
      (node (ref "J1") (pin "27") (pinfunction "27_27") (pintype "passive"))
    )
    (net (code "93") (name "unconnected-(J1-Pad31)") (class "Default")
      (node (ref "J1") (pin "31") (pinfunction "31_31") (pintype "passive"))
    )
    (net (code "94") (name "unconnected-(J1-Pad33)") (class "Default")
      (node (ref "J1") (pin "33") (pinfunction "33_33") (pintype "passive"))
    )
    (net (code "95") (name "unconnected-(J1-Pad37)") (class "Default")
      (node (ref "J1") (pin "37") (pinfunction "37_37") (pintype "passive"))
    )
    (net (code "96") (name "unconnected-(J1-Pad43)") (class "Default")
      (node (ref "J1") (pin "43") (pinfunction "43_43") (pintype "passive"))
    )
    (net (code "97") (name "unconnected-(J1-Pad45)") (class "Default")
      (node (ref "J1") (pin "45") (pinfunction "45_45") (pintype "passive"))
    )
    (net (code "98") (name "unconnected-(J1-Pad49)") (class "Default")
      (node (ref "J1") (pin "49") (pinfunction "49_49") (pintype "passive"))
    )
    (net (code "99") (name "unconnected-(J1-Pad51)") (class "Default")
      (node (ref "J1") (pin "51") (pinfunction "51_51") (pintype "passive"))
    )
    (net (code "100") (name "unconnected-(J1-Pad55)") (class "Default")
      (node (ref "J1") (pin "55") (pinfunction "55_55") (pintype "passive"))
    )
    (net (code "101") (name "unconnected-(J1-Pad57)") (class "Default")
      (node (ref "J1") (pin "57") (pinfunction "57_57") (pintype "passive"))
    )
    (net (code "102") (name "unconnected-(J1-Pad61)") (class "Default")
      (node (ref "J1") (pin "61") (pinfunction "61_61") (pintype "passive"))
    )
    (net (code "103") (name "unconnected-(J1-Pad63)") (class "Default")
      (node (ref "J1") (pin "63") (pinfunction "63_63") (pintype "passive"))
    )
    (net (code "104") (name "unconnected-(J1-Pad67)") (class "Default")
      (node (ref "J1") (pin "67") (pinfunction "67_67") (pintype "passive"))
    )
    (net (code "105") (name "unconnected-(J1-Pad69)") (class "Default")
      (node (ref "J1") (pin "69") (pinfunction "69_69") (pintype "passive"))
    )
    (net (code "106") (name "unconnected-(J1-Pad73)") (class "Default")
      (node (ref "J1") (pin "73") (pinfunction "73_73") (pintype "passive"))
    )
    (net (code "107") (name "unconnected-(J1-Pad75)") (class "Default")
      (node (ref "J1") (pin "75") (pinfunction "75_75") (pintype "passive"))
    )
    (net (code "108") (name "unconnected-(U2-Pad6)") (class "Default")
      (node (ref "U2") (pin "6") (pinfunction "6_6") (pintype "no_connect"))
    )
    (net (code "109") (name "unconnected-(U3-Pad6)") (class "Default")
      (node (ref "U3") (pin "6") (pinfunction "6_6") (pintype "no_connect"))
    )
    (net (code "110") (name "unconnected-(U4-PD-Pad7)") (class "Default")
      (node (ref "U4") (pin "7") (pinfunction "PD_7") (pintype "input"))
    )
    (net (code "111") (name "unconnected-(U5-PD-Pad7)") (class "Default")
      (node (ref "U5") (pin "7") (pinfunction "PD_7") (pintype "input"))
    )
    (net (code "112") (name "unconnected-(U6-PD-Pad7)") (class "Default")
      (node (ref "U6") (pin "7") (pinfunction "PD_7") (pintype "input"))
    )
    (net (code "113") (name "unconnected-(U7-PD-Pad7)") (class "Default")
      (node (ref "U7") (pin "7") (pinfunction "PD_7") (pintype "input"))
    )
    (net (code "114") (name "unconnected-(X3-NC-Pad1)") (class "Default")
      (node (ref "X3") (pin "1") (pinfunction "NC_1") (pintype "no_connect"))
    )
    (net (code "115") (name "~{CS}") (class "Default")
      (node (ref "J1") (pin "24") (pinfunction "24_24") (pintype "passive"))
      (node (ref "U1") (pin "15") (pinfunction "/CS_15") (pintype "input"))
    )
    (net (code "116") (name "~{SHDN}") (class "Default")
      (node (ref "J1") (pin "17") (pinfunction "17_17") (pintype "passive"))
      (node (ref "U1") (pin "12") (pinfunction "/SHDN_12") (pintype "input"))
    )
  )
)
